# ADS1299-shield.net
KiCad netlist of a schematic drawn in EAGLE
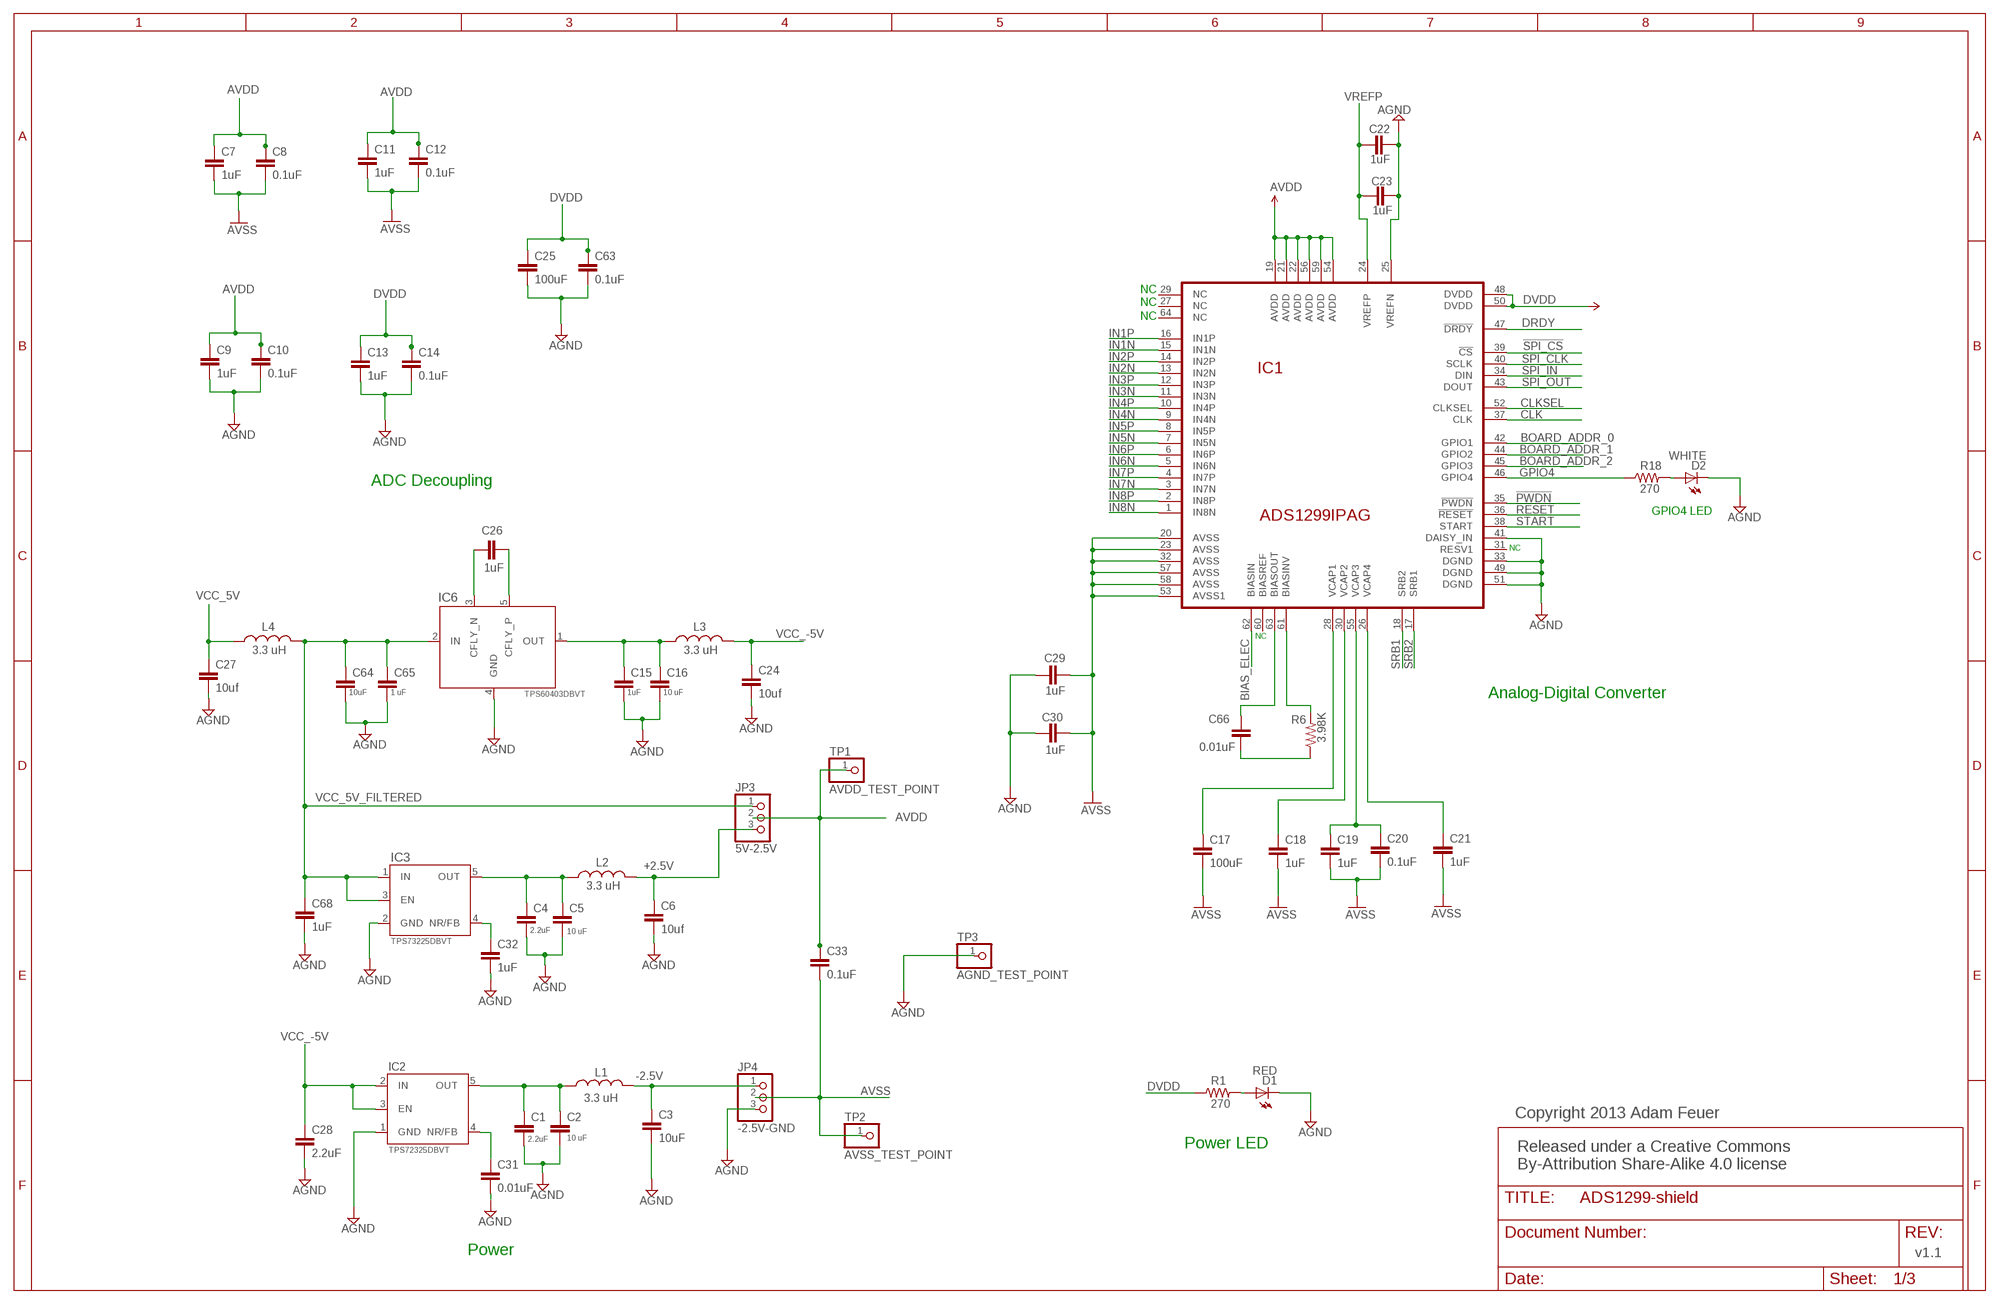
[diagram p0: schematic, sheet 1]
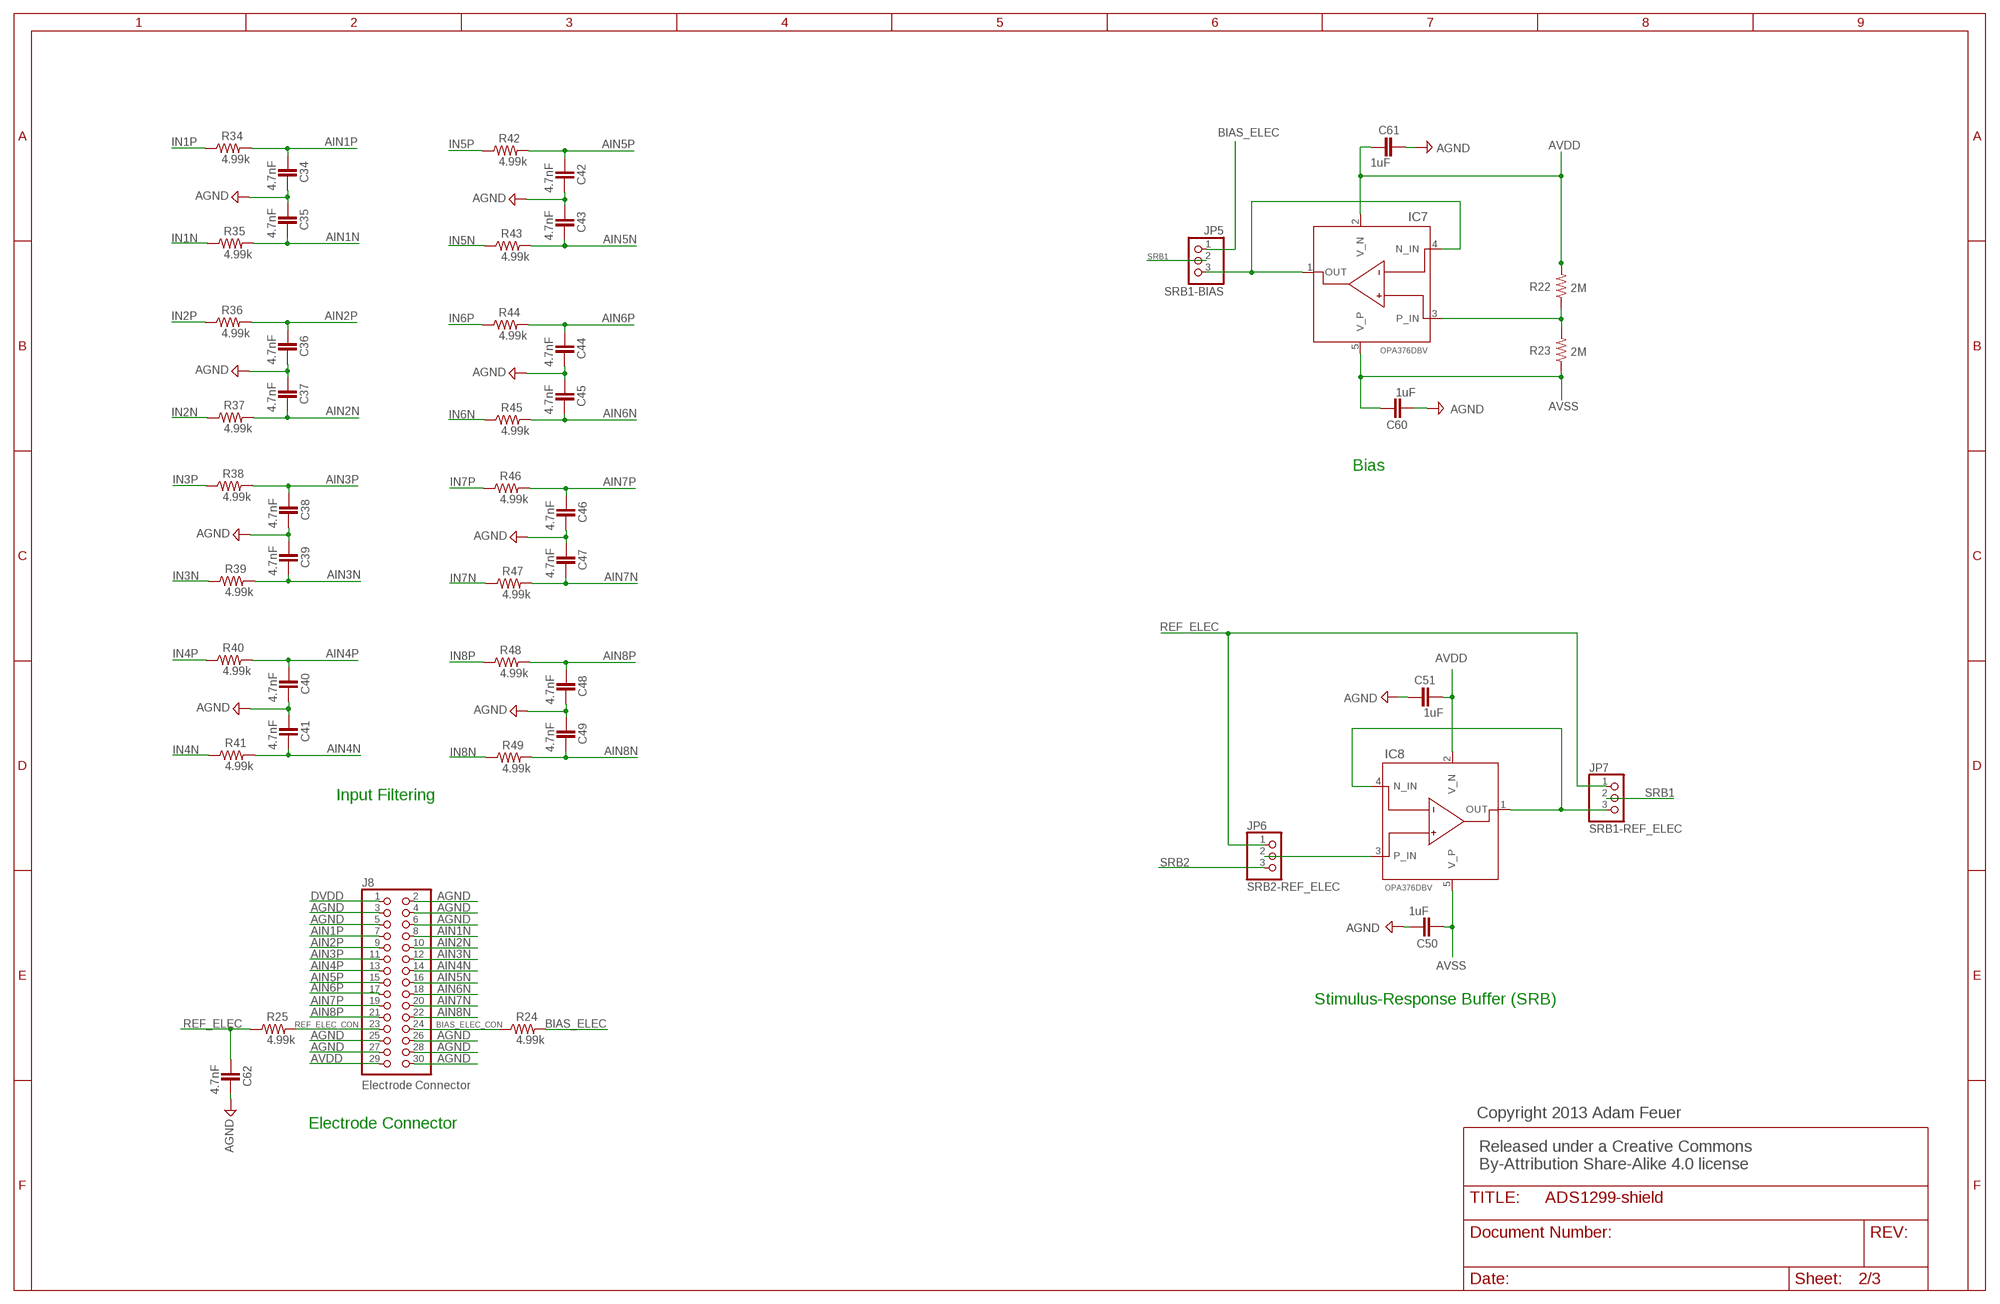
[diagram p1: schematic, sheet 2]
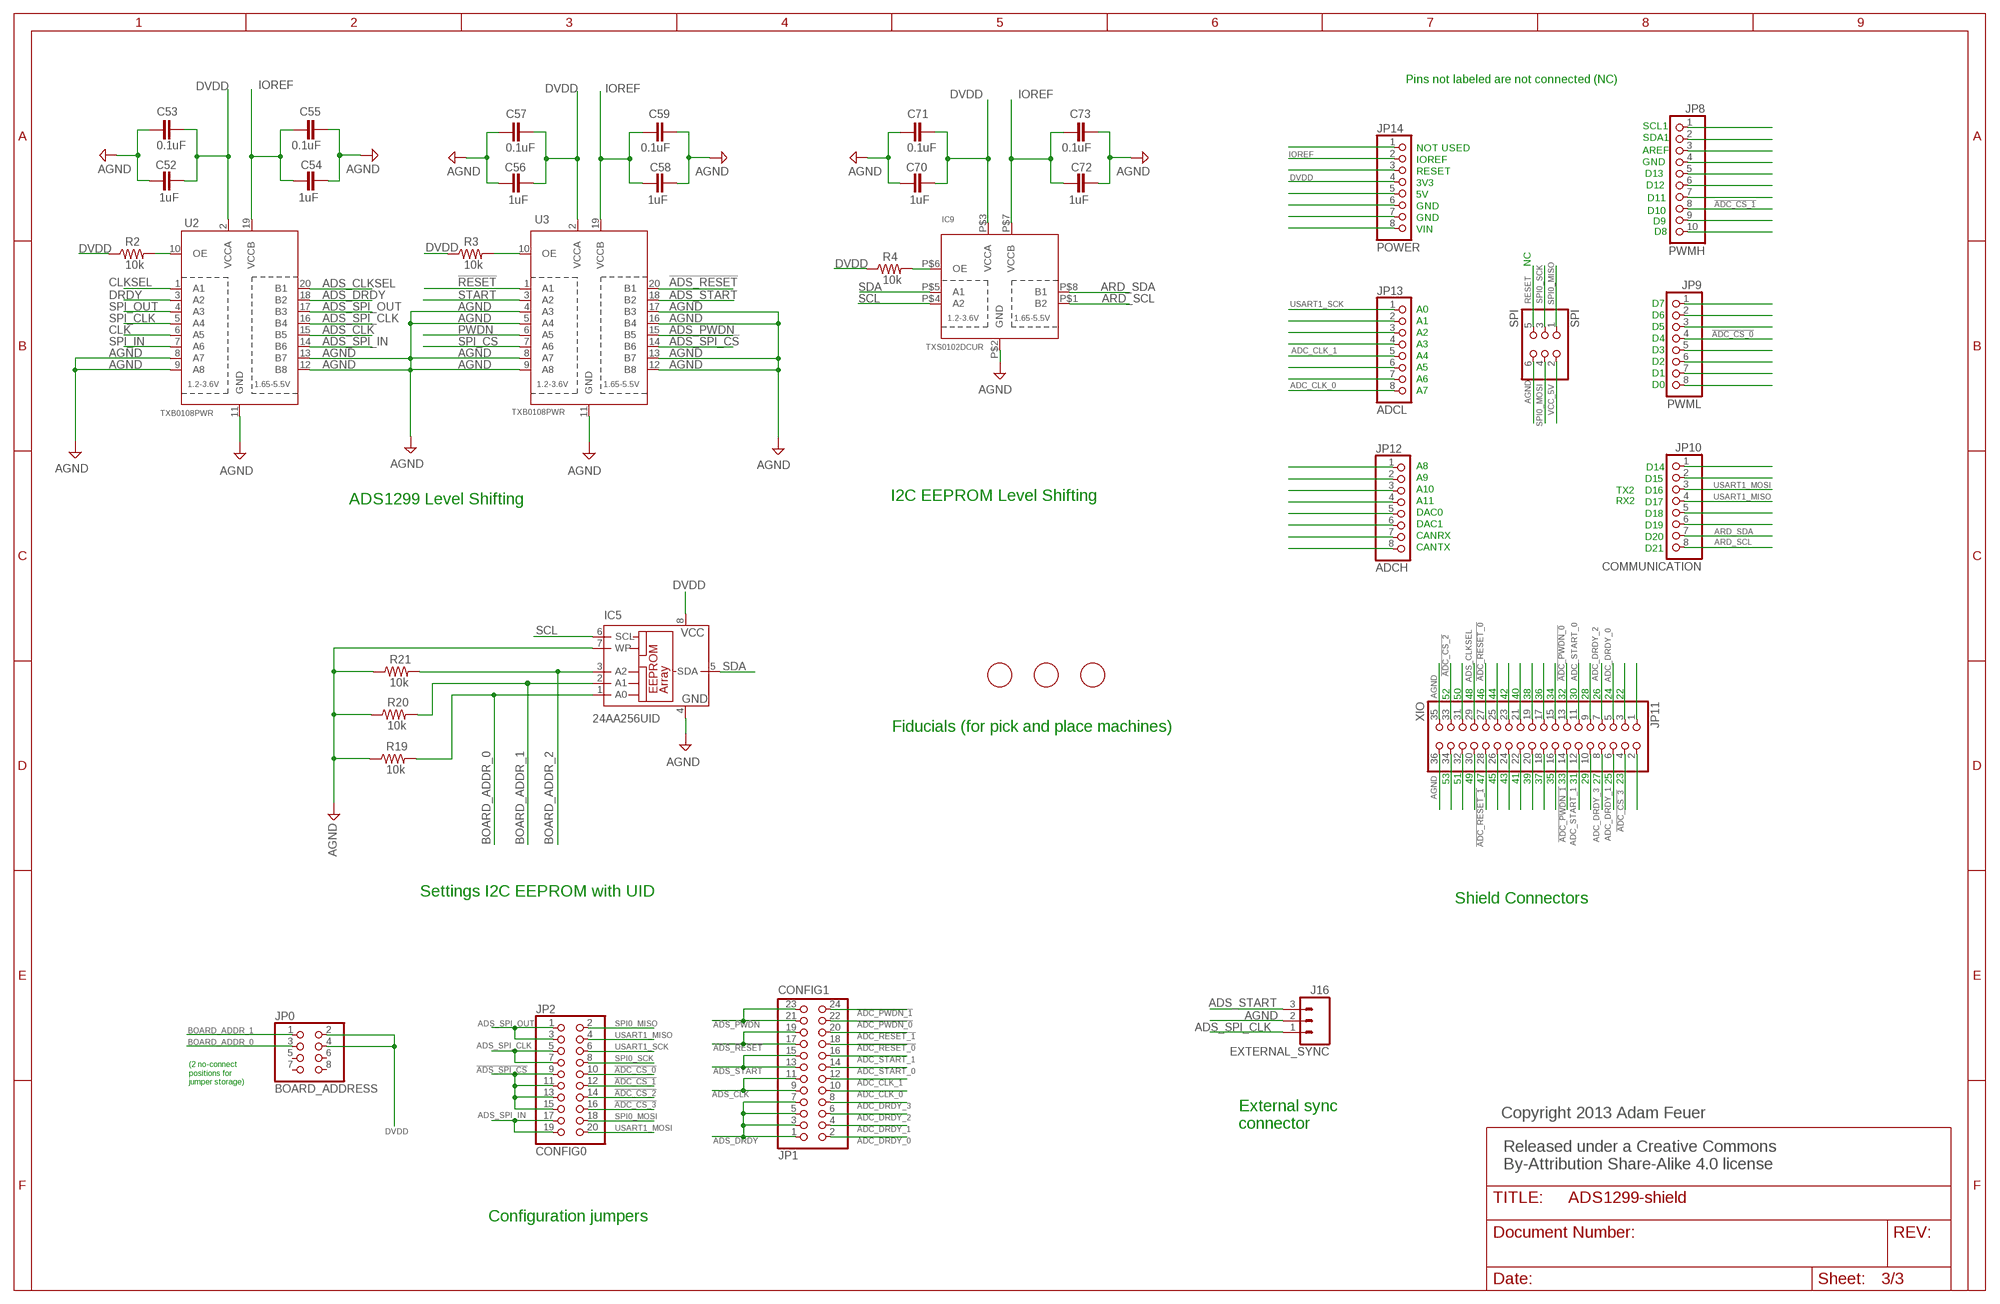
[diagram p2: schematic, sheet 3]

(export (version "E")
  (design (tool "Eeschema 10.0.6"))
  (components
    (comp (ref "C52")
      (value "1uF")
      (footprint "eagle-import:0603-CAP")
      (libsource (lib "eagle-import") (part "CAP0603-CAP"))
    )
    (comp (ref "C53")
      (value "0.1uF")
      (footprint "eagle-import:0603-CAP")
      (libsource (lib "eagle-import") (part "CAP0603-CAP"))
    )
    (comp (ref "C54")
      (value "1uF")
      (footprint "eagle-import:0603-CAP")
      (libsource (lib "eagle-import") (part "CAP0603-CAP"))
    )
    (comp (ref "C55")
      (value "0.1uF")
      (footprint "eagle-import:0603-CAP")
      (libsource (lib "eagle-import") (part "CAP0603-CAP"))
    )
    (comp (ref "C56")
      (value "1uF")
      (footprint "eagle-import:0603-CAP")
      (libsource (lib "eagle-import") (part "CAP0603-CAP"))
    )
    (comp (ref "C57")
      (value "0.1uF")
      (footprint "eagle-import:0603-CAP")
      (libsource (lib "eagle-import") (part "CAP0603-CAP"))
    )
    (comp (ref "C58")
      (value "1uF")
      (footprint "eagle-import:0603-CAP")
      (libsource (lib "eagle-import") (part "CAP0603-CAP"))
    )
    (comp (ref "C59")
      (value "0.1uF")
      (footprint "eagle-import:0603-CAP")
      (libsource (lib "eagle-import") (part "CAP0603-CAP"))
    )
    (comp (ref "C70")
      (value "1uF")
      (footprint "eagle-import:0603-CAP")
      (libsource (lib "eagle-import") (part "CAP0603-CAP"))
    )
    (comp (ref "C71")
      (value "0.1uF")
      (footprint "eagle-import:0603-CAP")
      (libsource (lib "eagle-import") (part "CAP0603-CAP"))
    )
    (comp (ref "C72")
      (value "1uF")
      (footprint "eagle-import:0603-CAP")
      (libsource (lib "eagle-import") (part "CAP0603-CAP"))
    )
    (comp (ref "C73")
      (value "0.1uF")
      (footprint "eagle-import:0603-CAP")
      (libsource (lib "eagle-import") (part "CAP0603-CAP"))
    )
    (comp (ref "IC5")
      (value "24AA256UID")
      (footprint "eagle-import:SO-08")
      (fields (field (name "MF") "MICROCHIP") (field (name "MPN") "24LC256-I/SN"))
      (libsource (lib "eagle-import") (part "24SNLC256"))
    )
    (comp (ref "IC9")
      (value "TXS0102DCUR")
      (footprint "eagle-import:VFSOP-8")
      (libsource (lib "eagle-import") (part "TXS0102"))
    )
    (comp (ref "J16")
      (value "EXTERNAL_SYNC")
      (footprint "eagle-import:JST-3-PTH")
      (libsource (lib "eagle-import") (part "M03JST-PTH"))
    )
    (comp (ref "JP0")
      (value "BOARD_ADDRESS")
      (footprint "eagle-import:2X04")
      (libsource (lib "eagle-import") (part "PINHD-2X4"))
    )
    (comp (ref "JP1")
      (value "CONFIG1")
      (footprint "eagle-import:2X12")
      (libsource (lib "eagle-import") (part "PINHD-2X12"))
    )
    (comp (ref "JP2")
      (value "CONFIG0")
      (footprint "eagle-import:2X10")
      (libsource (lib "eagle-import") (part "PINHD-2X10"))
    )
    (comp (ref "JP8")
      (value "PWMH")
      (footprint "eagle-import:1X10")
      (libsource (lib "eagle-import") (part "PINHD-1X10"))
    )
    (comp (ref "JP9")
      (value "PWML")
      (footprint "eagle-import:1X08")
      (libsource (lib "eagle-import") (part "PINHD-1X8"))
    )
    (comp (ref "JP10")
      (value "COMMUNICATION")
      (footprint "eagle-import:1X08")
      (libsource (lib "eagle-import") (part "PINHD-1X8"))
    )
    (comp (ref "JP11")
      (value "XIO")
      (footprint "eagle-import:2X18")
      (libsource (lib "eagle-import") (part "PINHD-2X18"))
    )
    (comp (ref "JP12")
      (value "ADCH")
      (footprint "eagle-import:1X08")
      (libsource (lib "eagle-import") (part "PINHD-1X8"))
    )
    (comp (ref "JP13")
      (value "ADCL")
      (footprint "eagle-import:1X08")
      (libsource (lib "eagle-import") (part "PINHD-1X8"))
    )
    (comp (ref "JP14")
      (value "POWER")
      (footprint "eagle-import:1X08")
      (libsource (lib "eagle-import") (part "PINHD-1X8"))
    )
    (comp (ref "R2")
      (value "10k")
      (footprint "eagle-import:0603-RES")
      (libsource (lib "eagle-import") (part "RESISTOR0603-RES"))
    )
    (comp (ref "R3")
      (value "10k")
      (footprint "eagle-import:0603-RES")
      (libsource (lib "eagle-import") (part "RESISTOR0603-RES"))
    )
    (comp (ref "R4")
      (value "10k")
      (footprint "eagle-import:0603-RES")
      (libsource (lib "eagle-import") (part "RESISTOR0603-RES"))
    )
    (comp (ref "R19")
      (value "10k")
      (footprint "eagle-import:0603-RES")
      (libsource (lib "eagle-import") (part "RESISTOR0603-RES"))
    )
    (comp (ref "R20")
      (value "10k")
      (footprint "eagle-import:0603-RES")
      (libsource (lib "eagle-import") (part "RESISTOR0603-RES"))
    )
    (comp (ref "R21")
      (value "10k")
      (footprint "eagle-import:0603-RES")
      (libsource (lib "eagle-import") (part "RESISTOR0603-RES"))
    )
    (comp (ref "SPI")
      (value "SPI")
      (footprint "eagle-import:2X03")
      (libsource (lib "eagle-import") (part "PINHD-2X3"))
    )
    (comp (ref "U$2")
      (value "FIDUCIAL")
      (footprint "eagle-import:FIDUCIAL_1MM")
      (libsource (lib "eagle-import") (part "FIDUCIAL"))
    )
    (comp (ref "U$5")
      (value "FIDUCIAL")
      (footprint "eagle-import:FIDUCIAL_1MM")
      (libsource (lib "eagle-import") (part "FIDUCIAL"))
    )
    (comp (ref "U$6")
      (value "FIDUCIAL")
      (footprint "eagle-import:FIDUCIAL_1MM")
      (libsource (lib "eagle-import") (part "FIDUCIAL"))
    )
    (comp (ref "U2")
      (value "TXB0108PWR")
      (footprint "eagle-import:TSSOP20")
      (libsource (lib "eagle-import") (part "TXB0108PWR"))
    )
    (comp (ref "U3")
      (value "TXB0108PWR")
      (footprint "eagle-import:TSSOP20")
      (libsource (lib "eagle-import") (part "TXB0108PWR"))
    )
    (comp (ref "C1")
      (value "2.2uF")
      (footprint "eagle-import:0603-CAP")
      (libsource (lib "eagle-import") (part "CAP0603-CAP"))
    )
    (comp (ref "C2")
      (value "10 uF")
      (footprint "eagle-import:0603-CAP")
      (libsource (lib "eagle-import") (part "CAP0603-CAP"))
    )
    (comp (ref "C3")
      (value "10uF")
      (footprint "eagle-import:0603-CAP")
      (libsource (lib "eagle-import") (part "CAP0603-CAP"))
    )
    (comp (ref "C4")
      (value "2.2uF")
      (footprint "eagle-import:0603-CAP")
      (libsource (lib "eagle-import") (part "CAP0603-CAP"))
    )
    (comp (ref "C5")
      (value "10 uF")
      (footprint "eagle-import:0603-CAP")
      (libsource (lib "eagle-import") (part "CAP0603-CAP"))
    )
    (comp (ref "C6")
      (value "10uf")
      (footprint "eagle-import:0603-CAP")
      (libsource (lib "eagle-import") (part "CAP0603-CAP"))
    )
    (comp (ref "C7")
      (value "1uF")
      (footprint "eagle-import:0603-CAP")
      (libsource (lib "eagle-import") (part "CAP0603-CAP"))
    )
    (comp (ref "C8")
      (value "0.1uF")
      (footprint "eagle-import:0603-CAP")
      (libsource (lib "eagle-import") (part "CAP0603-CAP"))
    )
    (comp (ref "C9")
      (value "1uF")
      (footprint "eagle-import:0603-CAP")
      (libsource (lib "eagle-import") (part "CAP0603-CAP"))
    )
    (comp (ref "C10")
      (value "0.1uF")
      (footprint "eagle-import:0603-CAP")
      (libsource (lib "eagle-import") (part "CAP0603-CAP"))
    )
    (comp (ref "C11")
      (value "1uF")
      (footprint "eagle-import:0603-CAP")
      (libsource (lib "eagle-import") (part "CAP0603-CAP"))
    )
    (comp (ref "C12")
      (value "0.1uF")
      (footprint "eagle-import:0603-CAP")
      (libsource (lib "eagle-import") (part "CAP0603-CAP"))
    )
    (comp (ref "C13")
      (value "1uF")
      (footprint "eagle-import:0603-CAP")
      (libsource (lib "eagle-import") (part "CAP0603-CAP"))
    )
    (comp (ref "C14")
      (value "0.1uF")
      (footprint "eagle-import:0603-CAP")
      (libsource (lib "eagle-import") (part "CAP0603-CAP"))
    )
    (comp (ref "C15")
      (value "1uF")
      (footprint "eagle-import:0603-CAP")
      (libsource (lib "eagle-import") (part "CAP0603-CAP"))
    )
    (comp (ref "C16")
      (value "10 uF")
      (footprint "eagle-import:0603-CAP")
      (libsource (lib "eagle-import") (part "CAP0603-CAP"))
    )
    (comp (ref "C17")
      (value "100uF")
      (footprint "eagle-import:1210")
      (libsource (lib "eagle-import") (part "CAP1210"))
    )
    (comp (ref "C18")
      (value "1uF")
      (footprint "eagle-import:0603-CAP")
      (libsource (lib "eagle-import") (part "CAP0603-CAP"))
    )
    (comp (ref "C19")
      (value "1uF")
      (footprint "eagle-import:0603-CAP")
      (libsource (lib "eagle-import") (part "CAP0603-CAP"))
    )
    (comp (ref "C20")
      (value "0.1uF")
      (footprint "eagle-import:0603-CAP")
      (libsource (lib "eagle-import") (part "CAP0603-CAP"))
    )
    (comp (ref "C21")
      (value "1uF")
      (footprint "eagle-import:0603-CAP")
      (libsource (lib "eagle-import") (part "CAP0603-CAP"))
    )
    (comp (ref "C22")
      (value "1uF")
      (footprint "eagle-import:0603-CAP")
      (libsource (lib "eagle-import") (part "CAP0603-CAP"))
    )
    (comp (ref "C23")
      (value "1uF")
      (footprint "eagle-import:0603-CAP")
      (libsource (lib "eagle-import") (part "CAP0603-CAP"))
    )
    (comp (ref "C24")
      (value "10uf")
      (footprint "eagle-import:0603-CAP")
      (libsource (lib "eagle-import") (part "CAP0603-CAP"))
    )
    (comp (ref "C25")
      (value "100uF")
      (footprint "eagle-import:1210")
      (libsource (lib "eagle-import") (part "CAP1210"))
    )
    (comp (ref "C26")
      (value "1uF")
      (footprint "eagle-import:0603-CAP")
      (libsource (lib "eagle-import") (part "CAP0603-CAP"))
    )
    (comp (ref "C27")
      (value "10uf")
      (footprint "eagle-import:0603-CAP")
      (libsource (lib "eagle-import") (part "CAP0603-CAP"))
    )
    (comp (ref "C28")
      (value "2.2uF")
      (footprint "eagle-import:0603-CAP")
      (libsource (lib "eagle-import") (part "CAP0603-CAP"))
    )
    (comp (ref "C29")
      (value "1uF")
      (footprint "eagle-import:0603-CAP")
      (libsource (lib "eagle-import") (part "CAP0603-CAP"))
    )
    (comp (ref "C30")
      (value "1uF")
      (footprint "eagle-import:0603-CAP")
      (libsource (lib "eagle-import") (part "CAP0603-CAP"))
    )
    (comp (ref "C31")
      (value "0.01uF")
      (footprint "eagle-import:0603-CAP")
      (libsource (lib "eagle-import") (part "CAP0603-CAP"))
    )
    (comp (ref "C32")
      (value "1uF")
      (footprint "eagle-import:0603-CAP")
      (libsource (lib "eagle-import") (part "CAP0603-CAP"))
    )
    (comp (ref "C33")
      (value "0.1uF")
      (footprint "eagle-import:0603-CAP")
      (libsource (lib "eagle-import") (part "CAP0603-CAP"))
    )
    (comp (ref "C63")
      (value "0.1uF")
      (footprint "eagle-import:0603-CAP")
      (libsource (lib "eagle-import") (part "CAP0603-CAP"))
    )
    (comp (ref "C64")
      (value "10uF")
      (footprint "eagle-import:0603-CAP")
      (libsource (lib "eagle-import") (part "CAP0603-CAP"))
    )
    (comp (ref "C65")
      (value "1 uF")
      (footprint "eagle-import:0603-CAP")
      (libsource (lib "eagle-import") (part "CAP0603-CAP"))
    )
    (comp (ref "C66")
      (value "0.01uF")
      (footprint "eagle-import:0603-CAP")
      (libsource (lib "eagle-import") (part "CAP0603-CAP"))
    )
    (comp (ref "C68")
      (value "1uF")
      (footprint "eagle-import:0603-CAP")
      (libsource (lib "eagle-import") (part "CAP0603-CAP"))
    )
    (comp (ref "D1")
      (value "RED")
      (footprint "eagle-import:LED-1206")
      (libsource (lib "eagle-import") (part "LED-RED1206"))
    )
    (comp (ref "D2")
      (value "WHITE")
      (footprint "eagle-import:LED-1206")
      (libsource (lib "eagle-import") (part "LED-WHITE"))
    )
    (comp (ref "IC1")
      (value "ADS1299IPAG")
      (footprint "eagle-import:TQFP64")
      (libsource (lib "eagle-import") (part "ADS1299PAG"))
    )
    (comp (ref "IC2")
      (value "TPS72325DBVT")
      (footprint "eagle-import:SOT23-5")
      (libsource (lib "eagle-import") (part "TPS723xx_TPS732XXDBV"))
    )
    (comp (ref "IC3")
      (value "TPS73225DBVT")
      (footprint "eagle-import:SOT23-5")
      (libsource (lib "eagle-import") (part "TPS732XXDBV"))
    )
    (comp (ref "IC6")
      (value "TPS60403DBVT")
      (footprint "eagle-import:SOT23-5")
      (libsource (lib "eagle-import") (part "TPS604XXDBV"))
    )
    (comp (ref "JP3")
      (value "5V-2.5V")
      (footprint "eagle-import:1X03")
      (libsource (lib "eagle-import") (part "headers_PINHD-1X3"))
    )
    (comp (ref "JP4")
      (value "-2.5V-GND")
      (footprint "eagle-import:1X03")
      (libsource (lib "eagle-import") (part "headers_PINHD-1X3"))
    )
    (comp (ref "L1")
      (value "3.3 uH")
      (footprint "eagle-import:0805")
      (libsource (lib "eagle-import") (part "INDUCTOR0805"))
    )
    (comp (ref "L2")
      (value "3.3 uH")
      (footprint "eagle-import:0805")
      (libsource (lib "eagle-import") (part "INDUCTOR0805"))
    )
    (comp (ref "L3")
      (value "3.3 uH")
      (footprint "eagle-import:0805")
      (libsource (lib "eagle-import") (part "INDUCTOR0805"))
    )
    (comp (ref "L4")
      (value "3.3 uH")
      (footprint "eagle-import:0805")
      (libsource (lib "eagle-import") (part "INDUCTOR0805"))
    )
    (comp (ref "R1")
      (value "270")
      (footprint "eagle-import:0603-RES")
      (libsource (lib "eagle-import") (part "RESISTOR0603-RES"))
    )
    (comp (ref "R6")
      (value "3.98K")
      (footprint "eagle-import:0603-RES")
      (libsource (lib "eagle-import") (part "RESISTOR0603-RES"))
    )
    (comp (ref "R18")
      (value "270")
      (footprint "eagle-import:0603-RES")
      (libsource (lib "eagle-import") (part "RESISTOR0603-RES"))
    )
    (comp (ref "TP1")
      (value "AVDD_TEST_POINT")
      (footprint "eagle-import:1X01")
      (libsource (lib "eagle-import") (part "PINHD-1X1"))
    )
    (comp (ref "TP2")
      (value "AVSS_TEST_POINT")
      (footprint "eagle-import:1X01")
      (libsource (lib "eagle-import") (part "PINHD-1X1"))
    )
    (comp (ref "TP3")
      (value "AGND_TEST_POINT")
      (footprint "eagle-import:1X01")
      (libsource (lib "eagle-import") (part "PINHD-1X1"))
    )
    (comp (ref "C34")
      (value "4.7nF")
      (footprint "eagle-import:0603-CAP")
      (libsource (lib "eagle-import") (part "CAP0603-CAP"))
    )
    (comp (ref "C35")
      (value "4.7nF")
      (footprint "eagle-import:0603-CAP")
      (libsource (lib "eagle-import") (part "CAP0603-CAP"))
    )
    (comp (ref "C36")
      (value "4.7nF")
      (footprint "eagle-import:0603-CAP")
      (libsource (lib "eagle-import") (part "CAP0603-CAP"))
    )
    (comp (ref "C37")
      (value "4.7nF")
      (footprint "eagle-import:0603-CAP")
      (libsource (lib "eagle-import") (part "CAP0603-CAP"))
    )
    (comp (ref "C38")
      (value "4.7nF")
      (footprint "eagle-import:0603-CAP")
      (libsource (lib "eagle-import") (part "CAP0603-CAP"))
    )
    (comp (ref "C39")
      (value "4.7nF")
      (footprint "eagle-import:0603-CAP")
      (libsource (lib "eagle-import") (part "CAP0603-CAP"))
    )
    (comp (ref "C40")
      (value "4.7nF")
      (footprint "eagle-import:0603-CAP")
      (libsource (lib "eagle-import") (part "CAP0603-CAP"))
    )
    (comp (ref "C41")
      (value "4.7nF")
      (footprint "eagle-import:0603-CAP")
      (libsource (lib "eagle-import") (part "CAP0603-CAP"))
    )
    (comp (ref "C42")
      (value "4.7nF")
      (footprint "eagle-import:0603-CAP")
      (libsource (lib "eagle-import") (part "CAP0603-CAP"))
    )
    (comp (ref "C43")
      (value "4.7nF")
      (footprint "eagle-import:0603-CAP")
      (libsource (lib "eagle-import") (part "CAP0603-CAP"))
    )
    (comp (ref "C44")
      (value "4.7nF")
      (footprint "eagle-import:0603-CAP")
      (libsource (lib "eagle-import") (part "CAP0603-CAP"))
    )
    (comp (ref "C45")
      (value "4.7nF")
      (footprint "eagle-import:0603-CAP")
      (libsource (lib "eagle-import") (part "CAP0603-CAP"))
    )
    (comp (ref "C46")
      (value "4.7nF")
      (footprint "eagle-import:0603-CAP")
      (libsource (lib "eagle-import") (part "CAP0603-CAP"))
    )
    (comp (ref "C47")
      (value "4.7nF")
      (footprint "eagle-import:0603-CAP")
      (libsource (lib "eagle-import") (part "CAP0603-CAP"))
    )
    (comp (ref "C48")
      (value "4.7nF")
      (footprint "eagle-import:0603-CAP")
      (libsource (lib "eagle-import") (part "CAP0603-CAP"))
    )
    (comp (ref "C49")
      (value "4.7nF")
      (footprint "eagle-import:0603-CAP")
      (libsource (lib "eagle-import") (part "CAP0603-CAP"))
    )
    (comp (ref "C50")
      (value "1uF")
      (footprint "eagle-import:0603-CAP")
      (libsource (lib "eagle-import") (part "CAP0603-CAP"))
    )
    (comp (ref "C51")
      (value "1uF")
      (footprint "eagle-import:0603-CAP")
      (libsource (lib "eagle-import") (part "CAP0603-CAP"))
    )
    (comp (ref "C60")
      (value "1uF")
      (footprint "eagle-import:0603-CAP")
      (libsource (lib "eagle-import") (part "CAP0603-CAP"))
    )
    (comp (ref "C61")
      (value "1uF")
      (footprint "eagle-import:0603-CAP")
      (libsource (lib "eagle-import") (part "CAP0603-CAP"))
    )
    (comp (ref "C62")
      (value "4.7nF")
      (footprint "eagle-import:0603-CAP")
      (libsource (lib "eagle-import") (part "CAP0603-CAP"))
    )
    (comp (ref "IC7")
      (value "OPA376DBV")
      (footprint "eagle-import:SOT23-5")
      (libsource (lib "eagle-import") (part "OPA376DBV"))
    )
    (comp (ref "IC8")
      (value "OPA376DBV")
      (footprint "eagle-import:SOT23-5")
      (libsource (lib "eagle-import") (part "OPA376DBV"))
    )
    (comp (ref "J8")
      (value "Electrode Connector")
      (footprint "eagle-import:2X15")
      (libsource (lib "eagle-import") (part "PINHD-2X15"))
    )
    (comp (ref "JP5")
      (value "SRB1-BIAS")
      (footprint "eagle-import:1X03")
      (libsource (lib "eagle-import") (part "PINHD-1X3"))
    )
    (comp (ref "JP6")
      (value "SRB2-REF_ELEC")
      (footprint "eagle-import:1X03")
      (libsource (lib "eagle-import") (part "PINHD-1X3"))
    )
    (comp (ref "JP7")
      (value "SRB1-REF_ELEC")
      (footprint "eagle-import:1X03")
      (libsource (lib "eagle-import") (part "PINHD-1X3"))
    )
    (comp (ref "R22")
      (value "2M")
      (footprint "eagle-import:0603-RES")
      (libsource (lib "eagle-import") (part "RESISTOR0603-RES"))
    )
    (comp (ref "R23")
      (value "2M")
      (footprint "eagle-import:0603-RES")
      (libsource (lib "eagle-import") (part "RESISTOR0603-RES"))
    )
    (comp (ref "R24")
      (value "4.99k")
      (footprint "eagle-import:0603-RES")
      (libsource (lib "eagle-import") (part "RESISTOR0603-RES"))
    )
    (comp (ref "R25")
      (value "4.99k")
      (footprint "eagle-import:0603-RES")
      (libsource (lib "eagle-import") (part "RESISTOR0603-RES"))
    )
    (comp (ref "R34")
      (value "4.99k")
      (footprint "eagle-import:0603-RES")
      (libsource (lib "eagle-import") (part "RESISTOR0603-RES"))
    )
    (comp (ref "R35")
      (value "4.99k")
      (footprint "eagle-import:0603-RES")
      (libsource (lib "eagle-import") (part "RESISTOR0603-RES"))
    )
    (comp (ref "R36")
      (value "4.99k")
      (footprint "eagle-import:0603-RES")
      (libsource (lib "eagle-import") (part "RESISTOR0603-RES"))
    )
    (comp (ref "R37")
      (value "4.99k")
      (footprint "eagle-import:0603-RES")
      (libsource (lib "eagle-import") (part "RESISTOR0603-RES"))
    )
    (comp (ref "R38")
      (value "4.99k")
      (footprint "eagle-import:0603-RES")
      (libsource (lib "eagle-import") (part "RESISTOR0603-RES"))
    )
    (comp (ref "R39")
      (value "4.99k")
      (footprint "eagle-import:0603-RES")
      (libsource (lib "eagle-import") (part "RESISTOR0603-RES"))
    )
    (comp (ref "R40")
      (value "4.99k")
      (footprint "eagle-import:0603-RES")
      (libsource (lib "eagle-import") (part "RESISTOR0603-RES"))
    )
    (comp (ref "R41")
      (value "4.99k")
      (footprint "eagle-import:0603-RES")
      (libsource (lib "eagle-import") (part "RESISTOR0603-RES"))
    )
    (comp (ref "R42")
      (value "4.99k")
      (footprint "eagle-import:0603-RES")
      (libsource (lib "eagle-import") (part "RESISTOR0603-RES"))
    )
    (comp (ref "R43")
      (value "4.99k")
      (footprint "eagle-import:0603-RES")
      (libsource (lib "eagle-import") (part "RESISTOR0603-RES"))
    )
    (comp (ref "R44")
      (value "4.99k")
      (footprint "eagle-import:0603-RES")
      (libsource (lib "eagle-import") (part "RESISTOR0603-RES"))
    )
    (comp (ref "R45")
      (value "4.99k")
      (footprint "eagle-import:0603-RES")
      (libsource (lib "eagle-import") (part "RESISTOR0603-RES"))
    )
    (comp (ref "R46")
      (value "4.99k")
      (footprint "eagle-import:0603-RES")
      (libsource (lib "eagle-import") (part "RESISTOR0603-RES"))
    )
    (comp (ref "R47")
      (value "4.99k")
      (footprint "eagle-import:0603-RES")
      (libsource (lib "eagle-import") (part "RESISTOR0603-RES"))
    )
    (comp (ref "R48")
      (value "4.99k")
      (footprint "eagle-import:0603-RES")
      (libsource (lib "eagle-import") (part "RESISTOR0603-RES"))
    )
    (comp (ref "R49")
      (value "4.99k")
      (footprint "eagle-import:0603-RES")
      (libsource (lib "eagle-import") (part "RESISTOR0603-RES"))
    )
  )
  (nets
    (net (code "1") (name "+2.5V") (class "Default")
      (node (ref "C6") (pin "1") (pinfunction "1_1") (pintype "passive"))
      (node (ref "JP3") (pin "3") (pinfunction "3_3") (pintype "passive"))
      (node (ref "L2") (pin "2") (pinfunction "2_2") (pintype "passive"))
    )
    (net (code "2") (name "-2.5V") (class "Default")
      (node (ref "C3") (pin "1") (pinfunction "1_1") (pintype "passive"))
      (node (ref "JP4") (pin "1") (pinfunction "1_1") (pintype "passive"))
      (node (ref "L1") (pin "2") (pinfunction "2_2") (pintype "passive"))
    )
    (net (code "3") (name "ADC_CLK_0") (class "Default")
      (node (ref "JP1") (pin "10") (pinfunction "10_10") (pintype "passive"))
      (node (ref "JP13") (pin "8") (pinfunction "8_8") (pintype "passive"))
    )
    (net (code "4") (name "ADC_CLK_1") (class "Default")
      (node (ref "JP1") (pin "12") (pinfunction "12_12") (pintype "passive"))
      (node (ref "JP13") (pin "5") (pinfunction "5_5") (pintype "passive"))
    )
    (net (code "5") (name "ADC_DRDY_0") (class "Default")
      (node (ref "JP1") (pin "2") (pinfunction "2_2") (pintype "passive"))
      (node (ref "JP11") (pin "5") (pinfunction "5_5") (pintype "passive"))
    )
    (net (code "6") (name "ADC_DRDY_1") (class "Default")
      (node (ref "JP1") (pin "4") (pinfunction "4_4") (pintype "passive"))
      (node (ref "JP11") (pin "6") (pinfunction "6_6") (pintype "passive"))
    )
    (net (code "7") (name "ADC_DRDY_2") (class "Default")
      (node (ref "JP1") (pin "6") (pinfunction "6_6") (pintype "passive"))
      (node (ref "JP11") (pin "7") (pinfunction "7_7") (pintype "passive"))
    )
    (net (code "8") (name "ADC_DRDY_3") (class "Default")
      (node (ref "JP1") (pin "8") (pinfunction "8_8") (pintype "passive"))
      (node (ref "JP11") (pin "8") (pinfunction "8_8") (pintype "passive"))
    )
    (net (code "9") (name "ADC_START_0") (class "Default")
      (node (ref "JP1") (pin "14") (pinfunction "14_14") (pintype "passive"))
      (node (ref "JP11") (pin "11") (pinfunction "11_11") (pintype "passive"))
    )
    (net (code "10") (name "ADC_START_1") (class "Default")
      (node (ref "JP1") (pin "16") (pinfunction "16_16") (pintype "passive"))
      (node (ref "JP11") (pin "12") (pinfunction "12_12") (pintype "passive"))
    )
    (net (code "11") (name "ADS_CLK") (class "Default")
      (node (ref "JP1") (pin "11") (pinfunction "11_11") (pintype "passive"))
      (node (ref "JP1") (pin "9") (pinfunction "9_9") (pintype "passive"))
      (node (ref "U2") (pin "15") (pinfunction "B5_15") (pintype "bidirectional"))
    )
    (net (code "12") (name "ADS_CLKSEL") (class "Default")
      (node (ref "JP11") (pin "29") (pinfunction "29_29") (pintype "passive"))
      (node (ref "U2") (pin "20") (pinfunction "B1_20") (pintype "bidirectional"))
    )
    (net (code "13") (name "ADS_DRDY") (class "Default")
      (node (ref "JP1") (pin "1") (pinfunction "1_1") (pintype "passive"))
      (node (ref "JP1") (pin "3") (pinfunction "3_3") (pintype "passive"))
      (node (ref "JP1") (pin "5") (pinfunction "5_5") (pintype "passive"))
      (node (ref "JP1") (pin "7") (pinfunction "7_7") (pintype "passive"))
      (node (ref "U2") (pin "18") (pinfunction "B2_18") (pintype "bidirectional"))
    )
    (net (code "14") (name "ADS_SPI_CLK") (class "Default")
      (node (ref "J16") (pin "1") (pinfunction "1_1") (pintype "passive"))
      (node (ref "JP2") (pin "5") (pinfunction "5_5") (pintype "passive"))
      (node (ref "JP2") (pin "7") (pinfunction "7_7") (pintype "passive"))
      (node (ref "U2") (pin "16") (pinfunction "B4_16") (pintype "bidirectional"))
    )
    (net (code "15") (name "ADS_SPI_IN") (class "Default")
      (node (ref "JP2") (pin "17") (pinfunction "17_17") (pintype "passive"))
      (node (ref "JP2") (pin "19") (pinfunction "19_19") (pintype "passive"))
      (node (ref "U2") (pin "14") (pinfunction "B6_14") (pintype "bidirectional"))
    )
    (net (code "16") (name "ADS_SPI_OUT") (class "Default")
      (node (ref "JP2") (pin "1") (pinfunction "1_1") (pintype "passive"))
      (node (ref "JP2") (pin "3") (pinfunction "3_3") (pintype "passive"))
      (node (ref "U2") (pin "17") (pinfunction "B3_17") (pintype "bidirectional"))
    )
    (net (code "17") (name "ADS_START") (class "Default")
      (node (ref "J16") (pin "3") (pinfunction "3_3") (pintype "passive"))
      (node (ref "JP1") (pin "13") (pinfunction "13_13") (pintype "passive"))
      (node (ref "JP1") (pin "15") (pinfunction "15_15") (pintype "passive"))
      (node (ref "U3") (pin "18") (pinfunction "B2_18") (pintype "bidirectional"))
    )
    (net (code "18") (name "AGND") (class "Default")
      (node (ref "C1") (pin "2") (pinfunction "2_2") (pintype "passive"))
      (node (ref "C10") (pin "2") (pinfunction "2_2") (pintype "passive"))
      (node (ref "C13") (pin "2") (pinfunction "2_2") (pintype "passive"))
      (node (ref "C14") (pin "2") (pinfunction "2_2") (pintype "passive"))
      (node (ref "C15") (pin "2") (pinfunction "2_2") (pintype "passive"))
      (node (ref "C16") (pin "2") (pinfunction "2_2") (pintype "passive"))
      (node (ref "C2") (pin "2") (pinfunction "2_2") (pintype "passive"))
      (node (ref "C22") (pin "2") (pinfunction "2_2") (pintype "passive"))
      (node (ref "C23") (pin "2") (pinfunction "2_2") (pintype "passive"))
      (node (ref "C24") (pin "2") (pinfunction "2_2") (pintype "passive"))
      (node (ref "C25") (pin "2") (pinfunction "2_2") (pintype "passive"))
      (node (ref "C27") (pin "2") (pinfunction "2_2") (pintype "passive"))
      (node (ref "C28") (pin "2") (pinfunction "2_2") (pintype "passive"))
      (node (ref "C29") (pin "1") (pinfunction "1_1") (pintype "passive"))
      (node (ref "C3") (pin "2") (pinfunction "2_2") (pintype "passive"))
      (node (ref "C30") (pin "1") (pinfunction "1_1") (pintype "passive"))
      (node (ref "C31") (pin "2") (pinfunction "2_2") (pintype "passive"))
      (node (ref "C32") (pin "2") (pinfunction "2_2") (pintype "passive"))
      (node (ref "C34") (pin "2") (pinfunction "2_2") (pintype "passive"))
      (node (ref "C35") (pin "1") (pinfunction "1_1") (pintype "passive"))
      (node (ref "C36") (pin "2") (pinfunction "2_2") (pintype "passive"))
      (node (ref "C37") (pin "1") (pinfunction "1_1") (pintype "passive"))
      (node (ref "C38") (pin "2") (pinfunction "2_2") (pintype "passive"))
      (node (ref "C39") (pin "1") (pinfunction "1_1") (pintype "passive"))
      (node (ref "C4") (pin "2") (pinfunction "2_2") (pintype "passive"))
      (node (ref "C40") (pin "2") (pinfunction "2_2") (pintype "passive"))
      (node (ref "C41") (pin "1") (pinfunction "1_1") (pintype "passive"))
      (node (ref "C42") (pin "2") (pinfunction "2_2") (pintype "passive"))
      (node (ref "C43") (pin "1") (pinfunction "1_1") (pintype "passive"))
      (node (ref "C44") (pin "2") (pinfunction "2_2") (pintype "passive"))
      (node (ref "C45") (pin "1") (pinfunction "1_1") (pintype "passive"))
      (node (ref "C46") (pin "2") (pinfunction "2_2") (pintype "passive"))
      (node (ref "C47") (pin "1") (pinfunction "1_1") (pintype "passive"))
      (node (ref "C48") (pin "2") (pinfunction "2_2") (pintype "passive"))
      (node (ref "C49") (pin "1") (pinfunction "1_1") (pintype "passive"))
      (node (ref "C5") (pin "2") (pinfunction "2_2") (pintype "passive"))
      (node (ref "C50") (pin "2") (pinfunction "2_2") (pintype "passive"))
      (node (ref "C51") (pin "1") (pinfunction "1_1") (pintype "passive"))
      (node (ref "C52") (pin "1") (pinfunction "1_1") (pintype "passive"))
      (node (ref "C53") (pin "1") (pinfunction "1_1") (pintype "passive"))
      (node (ref "C54") (pin "1") (pinfunction "1_1") (pintype "passive"))
      (node (ref "C55") (pin "1") (pinfunction "1_1") (pintype "passive"))
      (node (ref "C56") (pin "1") (pinfunction "1_1") (pintype "passive"))
      (node (ref "C57") (pin "1") (pinfunction "1_1") (pintype "passive"))
      (node (ref "C58") (pin "1") (pinfunction "1_1") (pintype "passive"))
      (node (ref "C59") (pin "1") (pinfunction "1_1") (pintype "passive"))
      (node (ref "C6") (pin "2") (pinfunction "2_2") (pintype "passive"))
      (node (ref "C60") (pin "2") (pinfunction "2_2") (pintype "passive"))
      (node (ref "C61") (pin "1") (pinfunction "1_1") (pintype "passive"))
      (node (ref "C62") (pin "2") (pinfunction "2_2") (pintype "passive"))
      (node (ref "C63") (pin "2") (pinfunction "2_2") (pintype "passive"))
      (node (ref "C64") (pin "2") (pinfunction "2_2") (pintype "passive"))
      (node (ref "C65") (pin "2") (pinfunction "2_2") (pintype "passive"))
      (node (ref "C68") (pin "2") (pinfunction "2_2") (pintype "passive"))
      (node (ref "C70") (pin "1") (pinfunction "1_1") (pintype "passive"))
      (node (ref "C71") (pin "1") (pinfunction "1_1") (pintype "passive"))
      (node (ref "C72") (pin "1") (pinfunction "1_1") (pintype "passive"))
      (node (ref "C73") (pin "1") (pinfunction "1_1") (pintype "passive"))
      (node (ref "C9") (pin "2") (pinfunction "2_2") (pintype "passive"))
      (node (ref "D1") (pin "C") (pinfunction "C_C") (pintype "passive"))
      (node (ref "D2") (pin "C") (pinfunction "C_C") (pintype "passive"))
      (node (ref "IC1") (pin "25") (pinfunction "VREFN_25") (pintype "bidirectional"))
      (node (ref "IC1") (pin "33") (pinfunction "DGND_33") (pintype "power_in"))
      (node (ref "IC1") (pin "41") (pinfunction "DAISY_IN_41") (pintype "input"))
      (node (ref "IC1") (pin "49") (pinfunction "DGND_49") (pintype "power_in"))
      (node (ref "IC1") (pin "51") (pinfunction "DGND_51") (pintype "power_in"))
      (node (ref "IC2") (pin "1") (pinfunction "GND_1") (pintype "bidirectional"))
      (node (ref "IC3") (pin "2") (pinfunction "GND_2") (pintype "bidirectional"))
      (node (ref "IC5") (pin "4") (pinfunction "GND_4") (pintype "power_in"))
      (node (ref "IC5") (pin "7") (pinfunction "WP_7") (pintype "input"))
      (node (ref "IC6") (pin "4") (pinfunction "GND_4") (pintype "bidirectional"))
      (node (ref "IC9") (pin "P$2") (pinfunction "GND_P$2") (pintype "bidirectional"))
      (node (ref "J16") (pin "2") (pinfunction "2_2") (pintype "passive"))
      (node (ref "J8") (pin "2") (pinfunction "2_2") (pintype "passive"))
      (node (ref "J8") (pin "25") (pinfunction "25_25") (pintype "passive"))
      (node (ref "J8") (pin "26") (pinfunction "26_26") (pintype "passive"))
      (node (ref "J8") (pin "27") (pinfunction "27_27") (pintype "passive"))
      (node (ref "J8") (pin "28") (pinfunction "28_28") (pintype "passive"))
      (node (ref "J8") (pin "3") (pinfunction "3_3") (pintype "passive"))
      (node (ref "J8") (pin "30") (pinfunction "30_30") (pintype "passive"))
      (node (ref "J8") (pin "4") (pinfunction "4_4") (pintype "passive"))
      (node (ref "J8") (pin "5") (pinfunction "5_5") (pintype "passive"))
      (node (ref "J8") (pin "6") (pinfunction "6_6") (pintype "passive"))
      (node (ref "JP11") (pin "35") (pinfunction "35_35") (pintype "passive"))
      (node (ref "JP11") (pin "36") (pinfunction "36_36") (pintype "passive"))
      (node (ref "JP4") (pin "3") (pinfunction "3_3") (pintype "passive"))
      (node (ref "R19") (pin "1") (pinfunction "1_1") (pintype "passive"))
      (node (ref "R20") (pin "1") (pinfunction "1_1") (pintype "passive"))
      (node (ref "R21") (pin "1") (pinfunction "1_1") (pintype "passive"))
      (node (ref "SPI") (pin "6") (pinfunction "6_6") (pintype "passive"))
      (node (ref "TP3") (pin "1") (pinfunction "1_1") (pintype "passive"))
      (node (ref "U2") (pin "11") (pinfunction "GND_11") (pintype "bidirectional"))
      (node (ref "U2") (pin "12") (pinfunction "B8_12") (pintype "bidirectional"))
      (node (ref "U2") (pin "13") (pinfunction "B7_13") (pintype "bidirectional"))
      (node (ref "U2") (pin "8") (pinfunction "A7_8") (pintype "bidirectional"))
      (node (ref "U2") (pin "9") (pinfunction "A8_9") (pintype "bidirectional"))
      (node (ref "U3") (pin "11") (pinfunction "GND_11") (pintype "bidirectional"))
      (node (ref "U3") (pin "12") (pinfunction "B8_12") (pintype "bidirectional"))
      (node (ref "U3") (pin "13") (pinfunction "B7_13") (pintype "bidirectional"))
      (node (ref "U3") (pin "16") (pinfunction "B4_16") (pintype "bidirectional"))
      (node (ref "U3") (pin "17") (pinfunction "B3_17") (pintype "bidirectional"))
      (node (ref "U3") (pin "4") (pinfunction "A3_4") (pintype "bidirectional"))
      (node (ref "U3") (pin "5") (pinfunction "A4_5") (pintype "bidirectional"))
      (node (ref "U3") (pin "8") (pinfunction "A7_8") (pintype "bidirectional"))
      (node (ref "U3") (pin "9") (pinfunction "A8_9") (pintype "bidirectional"))
    )
    (net (code "19") (name "AIN1N") (class "Default")
      (node (ref "C35") (pin "2") (pinfunction "2_2") (pintype "passive"))
      (node (ref "J8") (pin "8") (pinfunction "8_8") (pintype "passive"))
      (node (ref "R35") (pin "2") (pinfunction "2_2") (pintype "passive"))
    )
    (net (code "20") (name "AIN1P") (class "Default")
      (node (ref "C34") (pin "1") (pinfunction "1_1") (pintype "passive"))
      (node (ref "J8") (pin "7") (pinfunction "7_7") (pintype "passive"))
      (node (ref "R34") (pin "2") (pinfunction "2_2") (pintype "passive"))
    )
    (net (code "21") (name "AIN2N") (class "Default")
      (node (ref "C37") (pin "2") (pinfunction "2_2") (pintype "passive"))
      (node (ref "J8") (pin "10") (pinfunction "10_10") (pintype "passive"))
      (node (ref "R37") (pin "2") (pinfunction "2_2") (pintype "passive"))
    )
    (net (code "22") (name "AIN2P") (class "Default")
      (node (ref "C36") (pin "1") (pinfunction "1_1") (pintype "passive"))
      (node (ref "J8") (pin "9") (pinfunction "9_9") (pintype "passive"))
      (node (ref "R36") (pin "2") (pinfunction "2_2") (pintype "passive"))
    )
    (net (code "23") (name "AIN3N") (class "Default")
      (node (ref "C39") (pin "2") (pinfunction "2_2") (pintype "passive"))
      (node (ref "J8") (pin "12") (pinfunction "12_12") (pintype "passive"))
      (node (ref "R39") (pin "2") (pinfunction "2_2") (pintype "passive"))
    )
    (net (code "24") (name "AIN3P") (class "Default")
      (node (ref "C38") (pin "1") (pinfunction "1_1") (pintype "passive"))
      (node (ref "J8") (pin "11") (pinfunction "11_11") (pintype "passive"))
      (node (ref "R38") (pin "2") (pinfunction "2_2") (pintype "passive"))
    )
    (net (code "25") (name "AIN4N") (class "Default")
      (node (ref "C41") (pin "2") (pinfunction "2_2") (pintype "passive"))
      (node (ref "J8") (pin "14") (pinfunction "14_14") (pintype "passive"))
      (node (ref "R41") (pin "2") (pinfunction "2_2") (pintype "passive"))
    )
    (net (code "26") (name "AIN4P") (class "Default")
      (node (ref "C40") (pin "1") (pinfunction "1_1") (pintype "passive"))
      (node (ref "J8") (pin "13") (pinfunction "13_13") (pintype "passive"))
      (node (ref "R40") (pin "2") (pinfunction "2_2") (pintype "passive"))
    )
    (net (code "27") (name "AIN5N") (class "Default")
      (node (ref "C43") (pin "2") (pinfunction "2_2") (pintype "passive"))
      (node (ref "J8") (pin "16") (pinfunction "16_16") (pintype "passive"))
      (node (ref "R43") (pin "2") (pinfunction "2_2") (pintype "passive"))
    )
    (net (code "28") (name "AIN5P") (class "Default")
      (node (ref "C42") (pin "1") (pinfunction "1_1") (pintype "passive"))
      (node (ref "J8") (pin "15") (pinfunction "15_15") (pintype "passive"))
      (node (ref "R42") (pin "2") (pinfunction "2_2") (pintype "passive"))
    )
    (net (code "29") (name "AIN6N") (class "Default")
      (node (ref "C45") (pin "2") (pinfunction "2_2") (pintype "passive"))
      (node (ref "J8") (pin "18") (pinfunction "18_18") (pintype "passive"))
      (node (ref "R45") (pin "2") (pinfunction "2_2") (pintype "passive"))
    )
    (net (code "30") (name "AIN6P") (class "Default")
      (node (ref "C44") (pin "1") (pinfunction "1_1") (pintype "passive"))
      (node (ref "J8") (pin "17") (pinfunction "17_17") (pintype "passive"))
      (node (ref "R44") (pin "2") (pinfunction "2_2") (pintype "passive"))
    )
    (net (code "31") (name "AIN7N") (class "Default")
      (node (ref "C47") (pin "2") (pinfunction "2_2") (pintype "passive"))
      (node (ref "J8") (pin "20") (pinfunction "20_20") (pintype "passive"))
      (node (ref "R47") (pin "2") (pinfunction "2_2") (pintype "passive"))
    )
    (net (code "32") (name "AIN7P") (class "Default")
      (node (ref "C46") (pin "1") (pinfunction "1_1") (pintype "passive"))
      (node (ref "J8") (pin "19") (pinfunction "19_19") (pintype "passive"))
      (node (ref "R46") (pin "2") (pinfunction "2_2") (pintype "passive"))
    )
    (net (code "33") (name "AIN8N") (class "Default")
      (node (ref "C49") (pin "2") (pinfunction "2_2") (pintype "passive"))
      (node (ref "J8") (pin "22") (pinfunction "22_22") (pintype "passive"))
      (node (ref "R49") (pin "2") (pinfunction "2_2") (pintype "passive"))
    )
    (net (code "34") (name "AIN8P") (class "Default")
      (node (ref "C48") (pin "1") (pinfunction "1_1") (pintype "passive"))
      (node (ref "J8") (pin "21") (pinfunction "21_21") (pintype "passive"))
      (node (ref "R48") (pin "2") (pinfunction "2_2") (pintype "passive"))
    )
    (net (code "35") (name "ARD_SCL") (class "Default")
      (node (ref "IC9") (pin "P$1") (pinfunction "B2_P$1") (pintype "bidirectional"))
      (node (ref "JP10") (pin "8") (pinfunction "8_8") (pintype "passive"))
    )
    (net (code "36") (name "ARD_SDA") (class "Default")
      (node (ref "IC9") (pin "P$8") (pinfunction "B1_P$8") (pintype "bidirectional"))
      (node (ref "JP10") (pin "7") (pinfunction "7_7") (pintype "passive"))
    )
    (net (code "37") (name "AVDD") (class "Default")
      (node (ref "C10") (pin "1") (pinfunction "1_1") (pintype "passive"))
      (node (ref "C11") (pin "1") (pinfunction "1_1") (pintype "passive"))
      (node (ref "C12") (pin "1") (pinfunction "1_1") (pintype "passive"))
      (node (ref "C33") (pin "1") (pinfunction "1_1") (pintype "passive"))
      (node (ref "C51") (pin "2") (pinfunction "2_2") (pintype "passive"))
      (node (ref "C61") (pin "2") (pinfunction "2_2") (pintype "passive"))
      (node (ref "C7") (pin "1") (pinfunction "1_1") (pintype "passive"))
      (node (ref "C8") (pin "1") (pinfunction "1_1") (pintype "passive"))
      (node (ref "C9") (pin "1") (pinfunction "1_1") (pintype "passive"))
      (node (ref "IC1") (pin "19") (pinfunction "AVDD_19") (pintype "power_in"))
      (node (ref "IC1") (pin "21") (pinfunction "AVDD_21") (pintype "power_in"))
      (node (ref "IC1") (pin "22") (pinfunction "AVDD_22") (pintype "power_in"))
      (node (ref "IC1") (pin "54") (pinfunction "AVDD_54") (pintype "power_in"))
      (node (ref "IC1") (pin "56") (pinfunction "AVDD_56") (pintype "power_in"))
      (node (ref "IC1") (pin "59") (pinfunction "AVDD_59") (pintype "power_in"))
      (node (ref "IC7") (pin "2") (pinfunction "V_N_2") (pintype "bidirectional"))
      (node (ref "IC8") (pin "2") (pinfunction "V_N_2") (pintype "bidirectional"))
      (node (ref "J8") (pin "29") (pinfunction "29_29") (pintype "passive"))
      (node (ref "JP3") (pin "2") (pinfunction "2_2") (pintype "passive"))
      (node (ref "R22") (pin "2") (pinfunction "2_2") (pintype "passive"))
      (node (ref "TP1") (pin "1") (pinfunction "1_1") (pintype "passive"))
    )
    (net (code "38") (name "AVSS") (class "Default")
      (node (ref "C11") (pin "2") (pinfunction "2_2") (pintype "passive"))
      (node (ref "C12") (pin "2") (pinfunction "2_2") (pintype "passive"))
      (node (ref "C17") (pin "2") (pinfunction "2_2") (pintype "passive"))
      (node (ref "C18") (pin "2") (pinfunction "2_2") (pintype "passive"))
      (node (ref "C19") (pin "2") (pinfunction "2_2") (pintype "passive"))
      (node (ref "C20") (pin "2") (pinfunction "2_2") (pintype "passive"))
      (node (ref "C21") (pin "2") (pinfunction "2_2") (pintype "passive"))
      (node (ref "C29") (pin "2") (pinfunction "2_2") (pintype "passive"))
      (node (ref "C30") (pin "2") (pinfunction "2_2") (pintype "passive"))
      (node (ref "C33") (pin "2") (pinfunction "2_2") (pintype "passive"))
      (node (ref "C50") (pin "1") (pinfunction "1_1") (pintype "passive"))
      (node (ref "C60") (pin "1") (pinfunction "1_1") (pintype "passive"))
      (node (ref "C7") (pin "2") (pinfunction "2_2") (pintype "passive"))
      (node (ref "C8") (pin "2") (pinfunction "2_2") (pintype "passive"))
      (node (ref "IC1") (pin "20") (pinfunction "AVSS_20") (pintype "power_in"))
      (node (ref "IC1") (pin "23") (pinfunction "AVSS_23") (pintype "power_in"))
      (node (ref "IC1") (pin "32") (pinfunction "AVSS_32") (pintype "power_in"))
      (node (ref "IC1") (pin "53") (pinfunction "AVSS1_53") (pintype "power_in"))
      (node (ref "IC1") (pin "57") (pinfunction "AVSS_57") (pintype "power_in"))
      (node (ref "IC1") (pin "58") (pinfunction "AVSS_58") (pintype "power_in"))
      (node (ref "IC7") (pin "5") (pinfunction "V_P_5") (pintype "bidirectional"))
      (node (ref "IC8") (pin "5") (pinfunction "V_P_5") (pintype "bidirectional"))
      (node (ref "JP4") (pin "2") (pinfunction "2_2") (pintype "passive"))
      (node (ref "R23") (pin "1") (pinfunction "1_1") (pintype "passive"))
      (node (ref "TP2") (pin "1") (pinfunction "1_1") (pintype "passive"))
    )
    (net (code "39") (name "BIAS_ELEC") (class "Default")
      (node (ref "IC1") (pin "62") (pinfunction "BIASIN_62") (pintype "input"))
      (node (ref "JP5") (pin "1") (pinfunction "1_1") (pintype "passive"))
      (node (ref "R24") (pin "2") (pinfunction "2_2") (pintype "passive"))
    )
    (net (code "40") (name "BIAS_ELEC_CON") (class "Default")
      (node (ref "J8") (pin "24") (pinfunction "24_24") (pintype "passive"))
      (node (ref "R24") (pin "1") (pinfunction "1_1") (pintype "passive"))
    )
    (net (code "41") (name "BOARD_ADDR_0") (class "Default")
      (node (ref "IC1") (pin "42") (pinfunction "GPIO1_42") (pintype "bidirectional"))
      (node (ref "IC5") (pin "1") (pinfunction "A0_1") (pintype "input"))
      (node (ref "JP0") (pin "3") (pinfunction "3_3") (pintype "passive"))
      (node (ref "R19") (pin "2") (pinfunction "2_2") (pintype "passive"))
    )
    (net (code "42") (name "BOARD_ADDR_1") (class "Default")
      (node (ref "IC1") (pin "44") (pinfunction "GPIO2_44") (pintype "bidirectional"))
      (node (ref "IC5") (pin "2") (pinfunction "A1_2") (pintype "input"))
      (node (ref "JP0") (pin "1") (pinfunction "1_1") (pintype "passive"))
      (node (ref "R20") (pin "2") (pinfunction "2_2") (pintype "passive"))
    )
    (net (code "43") (name "BOARD_ADDR_2") (class "Default")
      (node (ref "IC1") (pin "45") (pinfunction "GPIO3_45") (pintype "bidirectional"))
      (node (ref "IC5") (pin "3") (pinfunction "A2_3") (pintype "input"))
      (node (ref "R21") (pin "2") (pinfunction "2_2") (pintype "passive"))
    )
    (net (code "44") (name "CLK") (class "Default")
      (node (ref "IC1") (pin "37") (pinfunction "CLK_37") (pintype "input"))
      (node (ref "U2") (pin "6") (pinfunction "A5_6") (pintype "bidirectional"))
    )
    (net (code "45") (name "CLKSEL") (class "Default")
      (node (ref "IC1") (pin "52") (pinfunction "CLKSEL_52") (pintype "input"))
      (node (ref "U2") (pin "1") (pinfunction "A1_1") (pintype "bidirectional"))
    )
    (net (code "46") (name "DRDY") (class "Default")
      (node (ref "IC1") (pin "47") (pinfunction "~{DRDY}_47") (pintype "output"))
      (node (ref "U2") (pin "3") (pinfunction "A2_3") (pintype "bidirectional"))
    )
    (net (code "47") (name "DVDD") (class "Default")
      (node (ref "C13") (pin "1") (pinfunction "1_1") (pintype "passive"))
      (node (ref "C14") (pin "1") (pinfunction "1_1") (pintype "passive"))
      (node (ref "C25") (pin "1") (pinfunction "1_1") (pintype "passive"))
      (node (ref "C52") (pin "2") (pinfunction "2_2") (pintype "passive"))
      (node (ref "C53") (pin "2") (pinfunction "2_2") (pintype "passive"))
      (node (ref "C56") (pin "2") (pinfunction "2_2") (pintype "passive"))
      (node (ref "C57") (pin "2") (pinfunction "2_2") (pintype "passive"))
      (node (ref "C63") (pin "1") (pinfunction "1_1") (pintype "passive"))
      (node (ref "C70") (pin "2") (pinfunction "2_2") (pintype "passive"))
      (node (ref "C71") (pin "2") (pinfunction "2_2") (pintype "passive"))
      (node (ref "IC1") (pin "48") (pinfunction "DVDD_48") (pintype "power_in"))
      (node (ref "IC1") (pin "50") (pinfunction "DVDD_50") (pintype "power_in"))
      (node (ref "IC5") (pin "8") (pinfunction "VCC_8") (pintype "power_in"))
      (node (ref "IC9") (pin "P$3") (pinfunction "VCCA_P$3") (pintype "bidirectional"))
      (node (ref "J8") (pin "1") (pinfunction "1_1") (pintype "passive"))
      (node (ref "JP0") (pin "2") (pinfunction "2_2") (pintype "passive"))
      (node (ref "JP0") (pin "4") (pinfunction "4_4") (pintype "passive"))
      (node (ref "JP14") (pin "4") (pinfunction "4_4") (pintype "passive"))
      (node (ref "R1") (pin "1") (pinfunction "1_1") (pintype "passive"))
      (node (ref "R2") (pin "1") (pinfunction "1_1") (pintype "passive"))
      (node (ref "R3") (pin "1") (pinfunction "1_1") (pintype "passive"))
      (node (ref "R4") (pin "1") (pinfunction "1_1") (pintype "passive"))
      (node (ref "U2") (pin "2") (pinfunction "VCCA_2") (pintype "bidirectional"))
      (node (ref "U3") (pin "2") (pinfunction "VCCA_2") (pintype "bidirectional"))
    )
    (net (code "48") (name "GPIO4") (class "Default")
      (node (ref "IC1") (pin "46") (pinfunction "GPIO4_46") (pintype "bidirectional"))
      (node (ref "R18") (pin "1") (pinfunction "1_1") (pintype "passive"))
    )
    (net (code "49") (name "IN1N") (class "Default")
      (node (ref "IC1") (pin "15") (pinfunction "IN1N_15") (pintype "input"))
      (node (ref "R35") (pin "1") (pinfunction "1_1") (pintype "passive"))
    )
    (net (code "50") (name "IN1P") (class "Default")
      (node (ref "IC1") (pin "16") (pinfunction "IN1P_16") (pintype "input"))
      (node (ref "R34") (pin "1") (pinfunction "1_1") (pintype "passive"))
    )
    (net (code "51") (name "IN2N") (class "Default")
      (node (ref "IC1") (pin "13") (pinfunction "IN2N_13") (pintype "input"))
      (node (ref "R37") (pin "1") (pinfunction "1_1") (pintype "passive"))
    )
    (net (code "52") (name "IN2P") (class "Default")
      (node (ref "IC1") (pin "14") (pinfunction "IN2P_14") (pintype "input"))
      (node (ref "R36") (pin "1") (pinfunction "1_1") (pintype "passive"))
    )
    (net (code "53") (name "IN3N") (class "Default")
      (node (ref "IC1") (pin "11") (pinfunction "IN3N_11") (pintype "input"))
      (node (ref "R39") (pin "1") (pinfunction "1_1") (pintype "passive"))
    )
    (net (code "54") (name "IN3P") (class "Default")
      (node (ref "IC1") (pin "12") (pinfunction "IN3P_12") (pintype "input"))
      (node (ref "R38") (pin "1") (pinfunction "1_1") (pintype "passive"))
    )
    (net (code "55") (name "IN4N") (class "Default")
      (node (ref "IC1") (pin "9") (pinfunction "IN4N_9") (pintype "input"))
      (node (ref "R41") (pin "1") (pinfunction "1_1") (pintype "passive"))
    )
    (net (code "56") (name "IN4P") (class "Default")
      (node (ref "IC1") (pin "10") (pinfunction "IN4P_10") (pintype "input"))
      (node (ref "R40") (pin "1") (pinfunction "1_1") (pintype "passive"))
    )
    (net (code "57") (name "IN5N") (class "Default")
      (node (ref "IC1") (pin "7") (pinfunction "IN5N_7") (pintype "input"))
      (node (ref "R43") (pin "1") (pinfunction "1_1") (pintype "passive"))
    )
    (net (code "58") (name "IN5P") (class "Default")
      (node (ref "IC1") (pin "8") (pinfunction "IN5P_8") (pintype "input"))
      (node (ref "R42") (pin "1") (pinfunction "1_1") (pintype "passive"))
    )
    (net (code "59") (name "IN6N") (class "Default")
      (node (ref "IC1") (pin "5") (pinfunction "IN6N_5") (pintype "input"))
      (node (ref "R45") (pin "1") (pinfunction "1_1") (pintype "passive"))
    )
    (net (code "60") (name "IN6P") (class "Default")
      (node (ref "IC1") (pin "6") (pinfunction "IN6P_6") (pintype "input"))
      (node (ref "R44") (pin "1") (pinfunction "1_1") (pintype "passive"))
    )
    (net (code "61") (name "IN7N") (class "Default")
      (node (ref "IC1") (pin "3") (pinfunction "IN7N_3") (pintype "input"))
      (node (ref "R47") (pin "1") (pinfunction "1_1") (pintype "passive"))
    )
    (net (code "62") (name "IN7P") (class "Default")
      (node (ref "IC1") (pin "4") (pinfunction "IN7P_4") (pintype "input"))
      (node (ref "R46") (pin "1") (pinfunction "1_1") (pintype "passive"))
    )
    (net (code "63") (name "IN8N") (class "Default")
      (node (ref "IC1") (pin "1") (pinfunction "IN8N_1") (pintype "input"))
      (node (ref "R49") (pin "1") (pinfunction "1_1") (pintype "passive"))
    )
    (net (code "64") (name "IN8P") (class "Default")
      (node (ref "IC1") (pin "2") (pinfunction "IN8P_2") (pintype "input"))
      (node (ref "R48") (pin "1") (pinfunction "1_1") (pintype "passive"))
    )
    (net (code "65") (name "IOREF") (class "Default")
      (node (ref "C54") (pin "2") (pinfunction "2_2") (pintype "passive"))
      (node (ref "C55") (pin "2") (pinfunction "2_2") (pintype "passive"))
      (node (ref "C58") (pin "2") (pinfunction "2_2") (pintype "passive"))
      (node (ref "C59") (pin "2") (pinfunction "2_2") (pintype "passive"))
      (node (ref "C72") (pin "2") (pinfunction "2_2") (pintype "passive"))
      (node (ref "C73") (pin "2") (pinfunction "2_2") (pintype "passive"))
      (node (ref "IC9") (pin "P$7") (pinfunction "VCCB_P$7") (pintype "bidirectional"))
      (node (ref "JP14") (pin "2") (pinfunction "2_2") (pintype "passive"))
      (node (ref "U2") (pin "19") (pinfunction "VCCB_19") (pintype "bidirectional"))
      (node (ref "U3") (pin "19") (pinfunction "VCCB_19") (pintype "bidirectional"))
    )
    (net (code "66") (name "Net-(C66-Pad2)") (class "Default")
      (node (ref "C66") (pin "2") (pinfunction "2_2") (pintype "passive"))
      (node (ref "R6") (pin "1") (pinfunction "1_1") (pintype "passive"))
    )
    (net (code "67") (name "Net-(D1-PadA)") (class "Default")
      (node (ref "D1") (pin "A") (pinfunction "A_A") (pintype "passive"))
      (node (ref "R1") (pin "2") (pinfunction "2_2") (pintype "passive"))
    )
    (net (code "68") (name "Net-(D2-PadA)") (class "Default")
      (node (ref "D2") (pin "A") (pinfunction "A_A") (pintype "passive"))
      (node (ref "R18") (pin "2") (pinfunction "2_2") (pintype "passive"))
    )
    (net (code "69") (name "Net-(IC1-BIASINV)") (class "Default")
      (node (ref "IC1") (pin "61") (pinfunction "BIASINV_61") (pintype "bidirectional"))
      (node (ref "R6") (pin "2") (pinfunction "2_2") (pintype "passive"))
    )
    (net (code "70") (name "Net-(IC1-BIASOUT)") (class "Default")
      (node (ref "C66") (pin "1") (pinfunction "1_1") (pintype "passive"))
      (node (ref "IC1") (pin "63") (pinfunction "BIASOUT_63") (pintype "output"))
    )
    (net (code "71") (name "Net-(IC1-VCAP1)") (class "Default")
      (node (ref "C17") (pin "1") (pinfunction "1_1") (pintype "passive"))
      (node (ref "IC1") (pin "28") (pinfunction "VCAP1_28") (pintype "bidirectional"))
    )
    (net (code "72") (name "Net-(IC1-VCAP2)") (class "Default")
      (node (ref "C18") (pin "1") (pinfunction "1_1") (pintype "passive"))
      (node (ref "IC1") (pin "30") (pinfunction "VCAP2_30") (pintype "bidirectional"))
    )
    (net (code "73") (name "Net-(IC1-VCAP3)") (class "Default")
      (node (ref "C19") (pin "1") (pinfunction "1_1") (pintype "passive"))
      (node (ref "C20") (pin "1") (pinfunction "1_1") (pintype "passive"))
      (node (ref "IC1") (pin "55") (pinfunction "VCAP3_55") (pintype "bidirectional"))
    )
    (net (code "74") (name "Net-(IC1-VCAP4)") (class "Default")
      (node (ref "C21") (pin "1") (pinfunction "1_1") (pintype "passive"))
      (node (ref "IC1") (pin "26") (pinfunction "VCAP4_26") (pintype "bidirectional"))
    )
    (net (code "75") (name "Net-(IC2-NR{slash}FB)") (class "Default")
      (node (ref "C31") (pin "1") (pinfunction "1_1") (pintype "passive"))
      (node (ref "IC2") (pin "4") (pinfunction "NR/FB_4") (pintype "bidirectional"))
    )
    (net (code "76") (name "Net-(IC2-OUT)") (class "Default")
      (node (ref "C1") (pin "1") (pinfunction "1_1") (pintype "passive"))
      (node (ref "C2") (pin "1") (pinfunction "1_1") (pintype "passive"))
      (node (ref "IC2") (pin "5") (pinfunction "OUT_5") (pintype "bidirectional"))
      (node (ref "L1") (pin "1") (pinfunction "1_1") (pintype "passive"))
    )
    (net (code "77") (name "Net-(IC3-NR{slash}FB)") (class "Default")
      (node (ref "C32") (pin "1") (pinfunction "1_1") (pintype "passive"))
      (node (ref "IC3") (pin "4") (pinfunction "NR/FB_4") (pintype "bidirectional"))
    )
    (net (code "78") (name "Net-(IC3-OUT)") (class "Default")
      (node (ref "C4") (pin "1") (pinfunction "1_1") (pintype "passive"))
      (node (ref "C5") (pin "1") (pinfunction "1_1") (pintype "passive"))
      (node (ref "IC3") (pin "5") (pinfunction "OUT_5") (pintype "bidirectional"))
      (node (ref "L2") (pin "1") (pinfunction "1_1") (pintype "passive"))
    )
    (net (code "79") (name "Net-(IC6-CFLY_N)") (class "Default")
      (node (ref "C26") (pin "1") (pinfunction "1_1") (pintype "passive"))
      (node (ref "IC6") (pin "3") (pinfunction "CFLY_N_3") (pintype "bidirectional"))
    )
    (net (code "80") (name "Net-(IC6-CFLY_P)") (class "Default")
      (node (ref "C26") (pin "2") (pinfunction "2_2") (pintype "passive"))
      (node (ref "IC6") (pin "5") (pinfunction "CFLY_P_5") (pintype "bidirectional"))
    )
    (net (code "81") (name "Net-(IC6-OUT)") (class "Default")
      (node (ref "C15") (pin "1") (pinfunction "1_1") (pintype "passive"))
      (node (ref "C16") (pin "1") (pinfunction "1_1") (pintype "passive"))
      (node (ref "IC6") (pin "1") (pinfunction "OUT_1") (pintype "bidirectional"))
      (node (ref "L3") (pin "1") (pinfunction "1_1") (pintype "passive"))
    )
    (net (code "82") (name "Net-(IC7-N_IN)") (class "Default")
      (node (ref "IC7") (pin "1") (pinfunction "OUT_1") (pintype "bidirectional"))
      (node (ref "IC7") (pin "4") (pinfunction "N_IN_4") (pintype "bidirectional"))
      (node (ref "JP5") (pin "3") (pinfunction "3_3") (pintype "passive"))
    )
    (net (code "83") (name "Net-(IC7-P_IN)") (class "Default")
      (node (ref "IC7") (pin "3") (pinfunction "P_IN_3") (pintype "bidirectional"))
      (node (ref "R22") (pin "1") (pinfunction "1_1") (pintype "passive"))
      (node (ref "R23") (pin "2") (pinfunction "2_2") (pintype "passive"))
    )
    (net (code "84") (name "Net-(IC8-N_IN)") (class "Default")
      (node (ref "IC8") (pin "1") (pinfunction "OUT_1") (pintype "bidirectional"))
      (node (ref "IC8") (pin "4") (pinfunction "N_IN_4") (pintype "bidirectional"))
      (node (ref "JP7") (pin "3") (pinfunction "3_3") (pintype "passive"))
    )
    (net (code "85") (name "Net-(IC8-P_IN)") (class "Default")
      (node (ref "IC8") (pin "3") (pinfunction "P_IN_3") (pintype "bidirectional"))
      (node (ref "JP6") (pin "2") (pinfunction "2_2") (pintype "passive"))
    )
    (net (code "86") (name "Net-(IC9-OE)") (class "Default")
      (node (ref "IC9") (pin "P$6") (pinfunction "OE_P$6") (pintype "bidirectional"))
      (node (ref "R4") (pin "2") (pinfunction "2_2") (pintype "passive"))
    )
    (net (code "87") (name "Net-(U2-OE)") (class "Default")
      (node (ref "R2") (pin "2") (pinfunction "2_2") (pintype "passive"))
      (node (ref "U2") (pin "10") (pinfunction "OE_10") (pintype "bidirectional"))
    )
    (net (code "88") (name "Net-(U3-OE)") (class "Default")
      (node (ref "R3") (pin "2") (pinfunction "2_2") (pintype "passive"))
      (node (ref "U3") (pin "10") (pinfunction "OE_10") (pintype "bidirectional"))
    )
    (net (code "89") (name "REF_ELEC") (class "Default")
      (node (ref "C62") (pin "1") (pinfunction "1_1") (pintype "passive"))
      (node (ref "JP6") (pin "1") (pinfunction "1_1") (pintype "passive"))
      (node (ref "JP7") (pin "1") (pinfunction "1_1") (pintype "passive"))
      (node (ref "R25") (pin "1") (pinfunction "1_1") (pintype "passive"))
    )
    (net (code "90") (name "REF_ELEC_CON") (class "Default")
      (node (ref "J8") (pin "23") (pinfunction "23_23") (pintype "passive"))
      (node (ref "R25") (pin "2") (pinfunction "2_2") (pintype "passive"))
    )
    (net (code "91") (name "RESET") (class "Default")
      (node (ref "SPI") (pin "5") (pinfunction "5_5") (pintype "passive"))
    )
    (net (code "92") (name "SCL") (class "Default")
      (node (ref "IC5") (pin "6") (pinfunction "SCL_6") (pintype "input"))
      (node (ref "IC9") (pin "P$4") (pinfunction "A2_P$4") (pintype "bidirectional"))
    )
    (net (code "93") (name "SDA") (class "Default")
      (node (ref "IC5") (pin "5") (pinfunction "SDA_5") (pintype "bidirectional"))
      (node (ref "IC9") (pin "P$5") (pinfunction "A1_P$5") (pintype "bidirectional"))
    )
    (net (code "94") (name "SPI0_MISO") (class "Default")
      (node (ref "JP2") (pin "2") (pinfunction "2_2") (pintype "passive"))
      (node (ref "SPI") (pin "1") (pinfunction "1_1") (pintype "passive"))
    )
    (net (code "95") (name "SPI0_MOSI") (class "Default")
      (node (ref "JP2") (pin "18") (pinfunction "18_18") (pintype "passive"))
      (node (ref "SPI") (pin "4") (pinfunction "4_4") (pintype "passive"))
    )
    (net (code "96") (name "SPI0_SCK") (class "Default")
      (node (ref "JP2") (pin "8") (pinfunction "8_8") (pintype "passive"))
      (node (ref "SPI") (pin "3") (pinfunction "3_3") (pintype "passive"))
    )
    (net (code "97") (name "SPI_CLK") (class "Default")
      (node (ref "IC1") (pin "40") (pinfunction "SCLK_40") (pintype "input"))
      (node (ref "U2") (pin "5") (pinfunction "A4_5") (pintype "bidirectional"))
    )
    (net (code "98") (name "SPI_IN") (class "Default")
      (node (ref "IC1") (pin "34") (pinfunction "DIN_34") (pintype "input"))
      (node (ref "U2") (pin "7") (pinfunction "A6_7") (pintype "bidirectional"))
    )
    (net (code "99") (name "SPI_OUT") (class "Default")
      (node (ref "IC1") (pin "43") (pinfunction "DOUT_43") (pintype "output"))
      (node (ref "U2") (pin "4") (pinfunction "A3_4") (pintype "bidirectional"))
    )
    (net (code "100") (name "SRB1") (class "Default")
      (node (ref "IC1") (pin "18") (pinfunction "SRB2_18") (pintype "output"))
      (node (ref "JP5") (pin "2") (pinfunction "2_2") (pintype "passive"))
      (node (ref "JP7") (pin "2") (pinfunction "2_2") (pintype "passive"))
    )
    (net (code "101") (name "SRB2") (class "Default")
      (node (ref "IC1") (pin "17") (pinfunction "SRB1_17") (pintype "output"))
      (node (ref "JP6") (pin "3") (pinfunction "3_3") (pintype "passive"))
    )
    (net (code "102") (name "START") (class "Default")
      (node (ref "IC1") (pin "38") (pinfunction "START_38") (pintype "input"))
      (node (ref "U3") (pin "3") (pinfunction "A2_3") (pintype "bidirectional"))
    )
    (net (code "103") (name "USART1_MISO") (class "Default")
      (node (ref "JP10") (pin "4") (pinfunction "4_4") (pintype "passive"))
      (node (ref "JP2") (pin "4") (pinfunction "4_4") (pintype "passive"))
    )
    (net (code "104") (name "USART1_MOSI") (class "Default")
      (node (ref "JP10") (pin "3") (pinfunction "3_3") (pintype "passive"))
      (node (ref "JP2") (pin "20") (pinfunction "20_20") (pintype "passive"))
    )
    (net (code "105") (name "USART1_SCK") (class "Default")
      (node (ref "JP13") (pin "1") (pinfunction "1_1") (pintype "passive"))
      (node (ref "JP2") (pin "6") (pinfunction "6_6") (pintype "passive"))
    )
    (net (code "106") (name "VCC_-5V") (class "Default")
      (node (ref "C24") (pin "1") (pinfunction "1_1") (pintype "passive"))
      (node (ref "C28") (pin "1") (pinfunction "1_1") (pintype "passive"))
      (node (ref "IC2") (pin "2") (pinfunction "IN_2") (pintype "bidirectional"))
      (node (ref "IC2") (pin "3") (pinfunction "EN_3") (pintype "bidirectional"))
      (node (ref "L3") (pin "2") (pinfunction "2_2") (pintype "passive"))
    )
    (net (code "107") (name "VCC_5V") (class "Default")
      (node (ref "C27") (pin "1") (pinfunction "1_1") (pintype "passive"))
      (node (ref "L4") (pin "1") (pinfunction "1_1") (pintype "passive"))
      (node (ref "SPI") (pin "2") (pinfunction "2_2") (pintype "passive"))
    )
    (net (code "108") (name "VCC_5V_FILTERED") (class "Default")
      (node (ref "C64") (pin "1") (pinfunction "1_1") (pintype "passive"))
      (node (ref "C65") (pin "1") (pinfunction "1_1") (pintype "passive"))
      (node (ref "C68") (pin "1") (pinfunction "1_1") (pintype "passive"))
      (node (ref "IC3") (pin "1") (pinfunction "IN_1") (pintype "bidirectional"))
      (node (ref "IC3") (pin "3") (pinfunction "EN_3") (pintype "bidirectional"))
      (node (ref "IC6") (pin "2") (pinfunction "IN_2") (pintype "bidirectional"))
      (node (ref "JP3") (pin "1") (pinfunction "1_1") (pintype "passive"))
      (node (ref "L4") (pin "2") (pinfunction "2_2") (pintype "passive"))
    )
    (net (code "109") (name "VREFP") (class "Default")
      (node (ref "C22") (pin "1") (pinfunction "1_1") (pintype "passive"))
      (node (ref "C23") (pin "1") (pinfunction "1_1") (pintype "passive"))
      (node (ref "IC1") (pin "24") (pinfunction "VREFP_24") (pintype "bidirectional"))
    )
    (net (code "110") (name "unconnected-(IC1-BIASREF-Pad60)") (class "Default")
      (node (ref "IC1") (pin "60") (pinfunction "BIASREF_60") (pintype "input"))
    )
    (net (code "111") (name "unconnected-(IC1-NC-Pad27)") (class "Default")
      (node (ref "IC1") (pin "27") (pinfunction "NC_27") (pintype "no_connect"))
    )
    (net (code "112") (name "unconnected-(IC1-NC-Pad29)") (class "Default")
      (node (ref "IC1") (pin "29") (pinfunction "NC_29") (pintype "no_connect"))
    )
    (net (code "113") (name "unconnected-(IC1-NC-Pad64)") (class "Default")
      (node (ref "IC1") (pin "64") (pinfunction "NC_64") (pintype "no_connect"))
    )
    (net (code "114") (name "unconnected-(IC1-RESV1-Pad31)") (class "Default")
      (node (ref "IC1") (pin "31") (pinfunction "RESV1_31") (pintype "no_connect"))
    )
    (net (code "115") (name "unconnected-(JP0-Pad5)") (class "Default")
      (node (ref "JP0") (pin "5") (pinfunction "5_5") (pintype "passive"))
    )
    (net (code "116") (name "unconnected-(JP0-Pad6)") (class "Default")
      (node (ref "JP0") (pin "6") (pinfunction "6_6") (pintype "passive"))
    )
    (net (code "117") (name "unconnected-(JP0-Pad7)") (class "Default")
      (node (ref "JP0") (pin "7") (pinfunction "7_7") (pintype "passive"))
    )
    (net (code "118") (name "unconnected-(JP0-Pad8)") (class "Default")
      (node (ref "JP0") (pin "8") (pinfunction "8_8") (pintype "passive"))
    )
    (net (code "119") (name "unconnected-(JP8-Pad1)") (class "Default")
      (node (ref "JP8") (pin "1") (pinfunction "1_1") (pintype "passive"))
    )
    (net (code "120") (name "unconnected-(JP8-Pad2)") (class "Default")
      (node (ref "JP8") (pin "2") (pinfunction "2_2") (pintype "passive"))
    )
    (net (code "121") (name "unconnected-(JP8-Pad3)") (class "Default")
      (node (ref "JP8") (pin "3") (pinfunction "3_3") (pintype "passive"))
    )
    (net (code "122") (name "unconnected-(JP8-Pad4)") (class "Default")
      (node (ref "JP8") (pin "4") (pinfunction "4_4") (pintype "passive"))
    )
    (net (code "123") (name "unconnected-(JP8-Pad5)") (class "Default")
      (node (ref "JP8") (pin "5") (pinfunction "5_5") (pintype "passive"))
    )
    (net (code "124") (name "unconnected-(JP8-Pad6)") (class "Default")
      (node (ref "JP8") (pin "6") (pinfunction "6_6") (pintype "passive"))
    )
    (net (code "125") (name "unconnected-(JP8-Pad7)") (class "Default")
      (node (ref "JP8") (pin "7") (pinfunction "7_7") (pintype "passive"))
    )
    (net (code "126") (name "unconnected-(JP8-Pad9)") (class "Default")
      (node (ref "JP8") (pin "9") (pinfunction "9_9") (pintype "passive"))
    )
    (net (code "127") (name "unconnected-(JP8-Pad10)") (class "Default")
      (node (ref "JP8") (pin "10") (pinfunction "10_10") (pintype "passive"))
    )
    (net (code "128") (name "unconnected-(JP9-Pad1)") (class "Default")
      (node (ref "JP9") (pin "1") (pinfunction "1_1") (pintype "passive"))
    )
    (net (code "129") (name "unconnected-(JP9-Pad2)") (class "Default")
      (node (ref "JP9") (pin "2") (pinfunction "2_2") (pintype "passive"))
    )
    (net (code "130") (name "unconnected-(JP9-Pad3)") (class "Default")
      (node (ref "JP9") (pin "3") (pinfunction "3_3") (pintype "passive"))
    )
    (net (code "131") (name "unconnected-(JP9-Pad5)") (class "Default")
      (node (ref "JP9") (pin "5") (pinfunction "5_5") (pintype "passive"))
    )
    (net (code "132") (name "unconnected-(JP9-Pad6)") (class "Default")
      (node (ref "JP9") (pin "6") (pinfunction "6_6") (pintype "passive"))
    )
    (net (code "133") (name "unconnected-(JP9-Pad7)") (class "Default")
      (node (ref "JP9") (pin "7") (pinfunction "7_7") (pintype "passive"))
    )
    (net (code "134") (name "unconnected-(JP9-Pad8)") (class "Default")
      (node (ref "JP9") (pin "8") (pinfunction "8_8") (pintype "passive"))
    )
    (net (code "135") (name "unconnected-(JP10-Pad1)") (class "Default")
      (node (ref "JP10") (pin "1") (pinfunction "1_1") (pintype "passive"))
    )
    (net (code "136") (name "unconnected-(JP10-Pad2)") (class "Default")
      (node (ref "JP10") (pin "2") (pinfunction "2_2") (pintype "passive"))
    )
    (net (code "137") (name "unconnected-(JP10-Pad5)") (class "Default")
      (node (ref "JP10") (pin "5") (pinfunction "5_5") (pintype "passive"))
    )
    (net (code "138") (name "unconnected-(JP10-Pad6)") (class "Default")
      (node (ref "JP10") (pin "6") (pinfunction "6_6") (pintype "passive"))
    )
    (net (code "139") (name "unconnected-(JP11-Pad1)") (class "Default")
      (node (ref "JP11") (pin "1") (pinfunction "1_1") (pintype "passive"))
    )
    (net (code "140") (name "unconnected-(JP11-Pad2)") (class "Default")
      (node (ref "JP11") (pin "2") (pinfunction "2_2") (pintype "passive"))
    )
    (net (code "141") (name "unconnected-(JP11-Pad3)") (class "Default")
      (node (ref "JP11") (pin "3") (pinfunction "3_3") (pintype "passive"))
    )
    (net (code "142") (name "unconnected-(JP11-Pad9)") (class "Default")
      (node (ref "JP11") (pin "9") (pinfunction "9_9") (pintype "passive"))
    )
    (net (code "143") (name "unconnected-(JP11-Pad10)") (class "Default")
      (node (ref "JP11") (pin "10") (pinfunction "10_10") (pintype "passive"))
    )
    (net (code "144") (name "unconnected-(JP11-Pad15)") (class "Default")
      (node (ref "JP11") (pin "15") (pinfunction "15_15") (pintype "passive"))
    )
    (net (code "145") (name "unconnected-(JP11-Pad16)") (class "Default")
      (node (ref "JP11") (pin "16") (pinfunction "16_16") (pintype "passive"))
    )
    (net (code "146") (name "unconnected-(JP11-Pad17)") (class "Default")
      (node (ref "JP11") (pin "17") (pinfunction "17_17") (pintype "passive"))
    )
    (net (code "147") (name "unconnected-(JP11-Pad18)") (class "Default")
      (node (ref "JP11") (pin "18") (pinfunction "18_18") (pintype "passive"))
    )
    (net (code "148") (name "unconnected-(JP11-Pad19)") (class "Default")
      (node (ref "JP11") (pin "19") (pinfunction "19_19") (pintype "passive"))
    )
    (net (code "149") (name "unconnected-(JP11-Pad20)") (class "Default")
      (node (ref "JP11") (pin "20") (pinfunction "20_20") (pintype "passive"))
    )
    (net (code "150") (name "unconnected-(JP11-Pad21)") (class "Default")
      (node (ref "JP11") (pin "21") (pinfunction "21_21") (pintype "passive"))
    )
    (net (code "151") (name "unconnected-(JP11-Pad22)") (class "Default")
      (node (ref "JP11") (pin "22") (pinfunction "22_22") (pintype "passive"))
    )
    (net (code "152") (name "unconnected-(JP11-Pad23)") (class "Default")
      (node (ref "JP11") (pin "23") (pinfunction "23_23") (pintype "passive"))
    )
    (net (code "153") (name "unconnected-(JP11-Pad24)") (class "Default")
      (node (ref "JP11") (pin "24") (pinfunction "24_24") (pintype "passive"))
    )
    (net (code "154") (name "unconnected-(JP11-Pad25)") (class "Default")
      (node (ref "JP11") (pin "25") (pinfunction "25_25") (pintype "passive"))
    )
    (net (code "155") (name "unconnected-(JP11-Pad26)") (class "Default")
      (node (ref "JP11") (pin "26") (pinfunction "26_26") (pintype "passive"))
    )
    (net (code "156") (name "unconnected-(JP11-Pad30)") (class "Default")
      (node (ref "JP11") (pin "30") (pinfunction "30_30") (pintype "passive"))
    )
    (net (code "157") (name "unconnected-(JP11-Pad31)") (class "Default")
      (node (ref "JP11") (pin "31") (pinfunction "31_31") (pintype "passive"))
    )
    (net (code "158") (name "unconnected-(JP11-Pad32)") (class "Default")
      (node (ref "JP11") (pin "32") (pinfunction "32_32") (pintype "passive"))
    )
    (net (code "159") (name "unconnected-(JP11-Pad34)") (class "Default")
      (node (ref "JP11") (pin "34") (pinfunction "34_34") (pintype "passive"))
    )
    (net (code "160") (name "unconnected-(JP12-Pad1)") (class "Default")
      (node (ref "JP12") (pin "1") (pinfunction "1_1") (pintype "passive"))
    )
    (net (code "161") (name "unconnected-(JP12-Pad2)") (class "Default")
      (node (ref "JP12") (pin "2") (pinfunction "2_2") (pintype "passive"))
    )
    (net (code "162") (name "unconnected-(JP12-Pad3)") (class "Default")
      (node (ref "JP12") (pin "3") (pinfunction "3_3") (pintype "passive"))
    )
    (net (code "163") (name "unconnected-(JP12-Pad4)") (class "Default")
      (node (ref "JP12") (pin "4") (pinfunction "4_4") (pintype "passive"))
    )
    (net (code "164") (name "unconnected-(JP12-Pad5)") (class "Default")
      (node (ref "JP12") (pin "5") (pinfunction "5_5") (pintype "passive"))
    )
    (net (code "165") (name "unconnected-(JP12-Pad6)") (class "Default")
      (node (ref "JP12") (pin "6") (pinfunction "6_6") (pintype "passive"))
    )
    (net (code "166") (name "unconnected-(JP12-Pad7)") (class "Default")
      (node (ref "JP12") (pin "7") (pinfunction "7_7") (pintype "passive"))
    )
    (net (code "167") (name "unconnected-(JP12-Pad8)") (class "Default")
      (node (ref "JP12") (pin "8") (pinfunction "8_8") (pintype "passive"))
    )
    (net (code "168") (name "unconnected-(JP13-Pad2)") (class "Default")
      (node (ref "JP13") (pin "2") (pinfunction "2_2") (pintype "passive"))
    )
    (net (code "169") (name "unconnected-(JP13-Pad3)") (class "Default")
      (node (ref "JP13") (pin "3") (pinfunction "3_3") (pintype "passive"))
    )
    (net (code "170") (name "unconnected-(JP13-Pad4)") (class "Default")
      (node (ref "JP13") (pin "4") (pinfunction "4_4") (pintype "passive"))
    )
    (net (code "171") (name "unconnected-(JP13-Pad6)") (class "Default")
      (node (ref "JP13") (pin "6") (pinfunction "6_6") (pintype "passive"))
    )
    (net (code "172") (name "unconnected-(JP13-Pad7)") (class "Default")
      (node (ref "JP13") (pin "7") (pinfunction "7_7") (pintype "passive"))
    )
    (net (code "173") (name "unconnected-(JP14-Pad1)") (class "Default")
      (node (ref "JP14") (pin "1") (pinfunction "1_1") (pintype "passive"))
    )
    (net (code "174") (name "unconnected-(JP14-Pad3)") (class "Default")
      (node (ref "JP14") (pin "3") (pinfunction "3_3") (pintype "passive"))
    )
    (net (code "175") (name "unconnected-(JP14-Pad5)") (class "Default")
      (node (ref "JP14") (pin "5") (pinfunction "5_5") (pintype "passive"))
    )
    (net (code "176") (name "unconnected-(JP14-Pad6)") (class "Default")
      (node (ref "JP14") (pin "6") (pinfunction "6_6") (pintype "passive"))
    )
    (net (code "177") (name "unconnected-(JP14-Pad7)") (class "Default")
      (node (ref "JP14") (pin "7") (pinfunction "7_7") (pintype "passive"))
    )
    (net (code "178") (name "unconnected-(JP14-Pad8)") (class "Default")
      (node (ref "JP14") (pin "8") (pinfunction "8_8") (pintype "passive"))
    )
    (net (code "179") (name "~{ADC_CS_0}") (class "Default")
      (node (ref "JP2") (pin "10") (pinfunction "10_10") (pintype "passive"))
      (node (ref "JP9") (pin "4") (pinfunction "4_4") (pintype "passive"))
    )
    (net (code "180") (name "~{ADC_CS_1}") (class "Default")
      (node (ref "JP2") (pin "12") (pinfunction "12_12") (pintype "passive"))
      (node (ref "JP8") (pin "8") (pinfunction "8_8") (pintype "passive"))
    )
    (net (code "181") (name "~{ADC_CS_2}") (class "Default")
      (node (ref "JP11") (pin "33") (pinfunction "33_33") (pintype "passive"))
      (node (ref "JP2") (pin "14") (pinfunction "14_14") (pintype "passive"))
    )
    (net (code "182") (name "~{ADC_CS_3}") (class "Default")
      (node (ref "JP11") (pin "4") (pinfunction "4_4") (pintype "passive"))
      (node (ref "JP2") (pin "16") (pinfunction "16_16") (pintype "passive"))
    )
    (net (code "183") (name "~{ADC_PWDN_0}") (class "Default")
      (node (ref "JP1") (pin "22") (pinfunction "22_22") (pintype "passive"))
      (node (ref "JP11") (pin "13") (pinfunction "13_13") (pintype "passive"))
    )
    (net (code "184") (name "~{ADC_PWDN_1}") (class "Default")
      (node (ref "JP1") (pin "24") (pinfunction "24_24") (pintype "passive"))
      (node (ref "JP11") (pin "14") (pinfunction "14_14") (pintype "passive"))
    )
    (net (code "185") (name "~{ADC_RESET_0}") (class "Default")
      (node (ref "JP1") (pin "18") (pinfunction "18_18") (pintype "passive"))
      (node (ref "JP11") (pin "27") (pinfunction "27_27") (pintype "passive"))
    )
    (net (code "186") (name "~{ADC_RESET_1}") (class "Default")
      (node (ref "JP1") (pin "20") (pinfunction "20_20") (pintype "passive"))
      (node (ref "JP11") (pin "28") (pinfunction "28_28") (pintype "passive"))
    )
    (net (code "187") (name "~{ADS_PWDN}") (class "Default")
      (node (ref "JP1") (pin "21") (pinfunction "21_21") (pintype "passive"))
      (node (ref "JP1") (pin "23") (pinfunction "23_23") (pintype "passive"))
      (node (ref "U3") (pin "15") (pinfunction "B5_15") (pintype "bidirectional"))
    )
    (net (code "188") (name "~{ADS_RESET}") (class "Default")
      (node (ref "JP1") (pin "17") (pinfunction "17_17") (pintype "passive"))
      (node (ref "JP1") (pin "19") (pinfunction "19_19") (pintype "passive"))
      (node (ref "U3") (pin "20") (pinfunction "B1_20") (pintype "bidirectional"))
    )
    (net (code "189") (name "~{ADS_SPI_CS}") (class "Default")
      (node (ref "JP2") (pin "11") (pinfunction "11_11") (pintype "passive"))
      (node (ref "JP2") (pin "13") (pinfunction "13_13") (pintype "passive"))
      (node (ref "JP2") (pin "15") (pinfunction "15_15") (pintype "passive"))
      (node (ref "JP2") (pin "9") (pinfunction "9_9") (pintype "passive"))
      (node (ref "U3") (pin "14") (pinfunction "B6_14") (pintype "bidirectional"))
    )
    (net (code "190") (name "~{PWDN}") (class "Default")
      (node (ref "IC1") (pin "35") (pinfunction "~{PWDN}_35") (pintype "input"))
      (node (ref "U3") (pin "6") (pinfunction "A5_6") (pintype "bidirectional"))
    )
    (net (code "191") (name "~{RESET}") (class "Default")
      (node (ref "IC1") (pin "36") (pinfunction "~{RESET}_36") (pintype "input"))
      (node (ref "U3") (pin "1") (pinfunction "A1_1") (pintype "bidirectional"))
    )
    (net (code "192") (name "~{SPI_CS}") (class "Default")
      (node (ref "IC1") (pin "39") (pinfunction "~{CS}_39") (pintype "input"))
      (node (ref "U3") (pin "7") (pinfunction "A6_7") (pintype "bidirectional"))
    )
  )
)
